# FRA_Sensor_v1.net
KiCad netlist of a schematic drawn in EAGLE
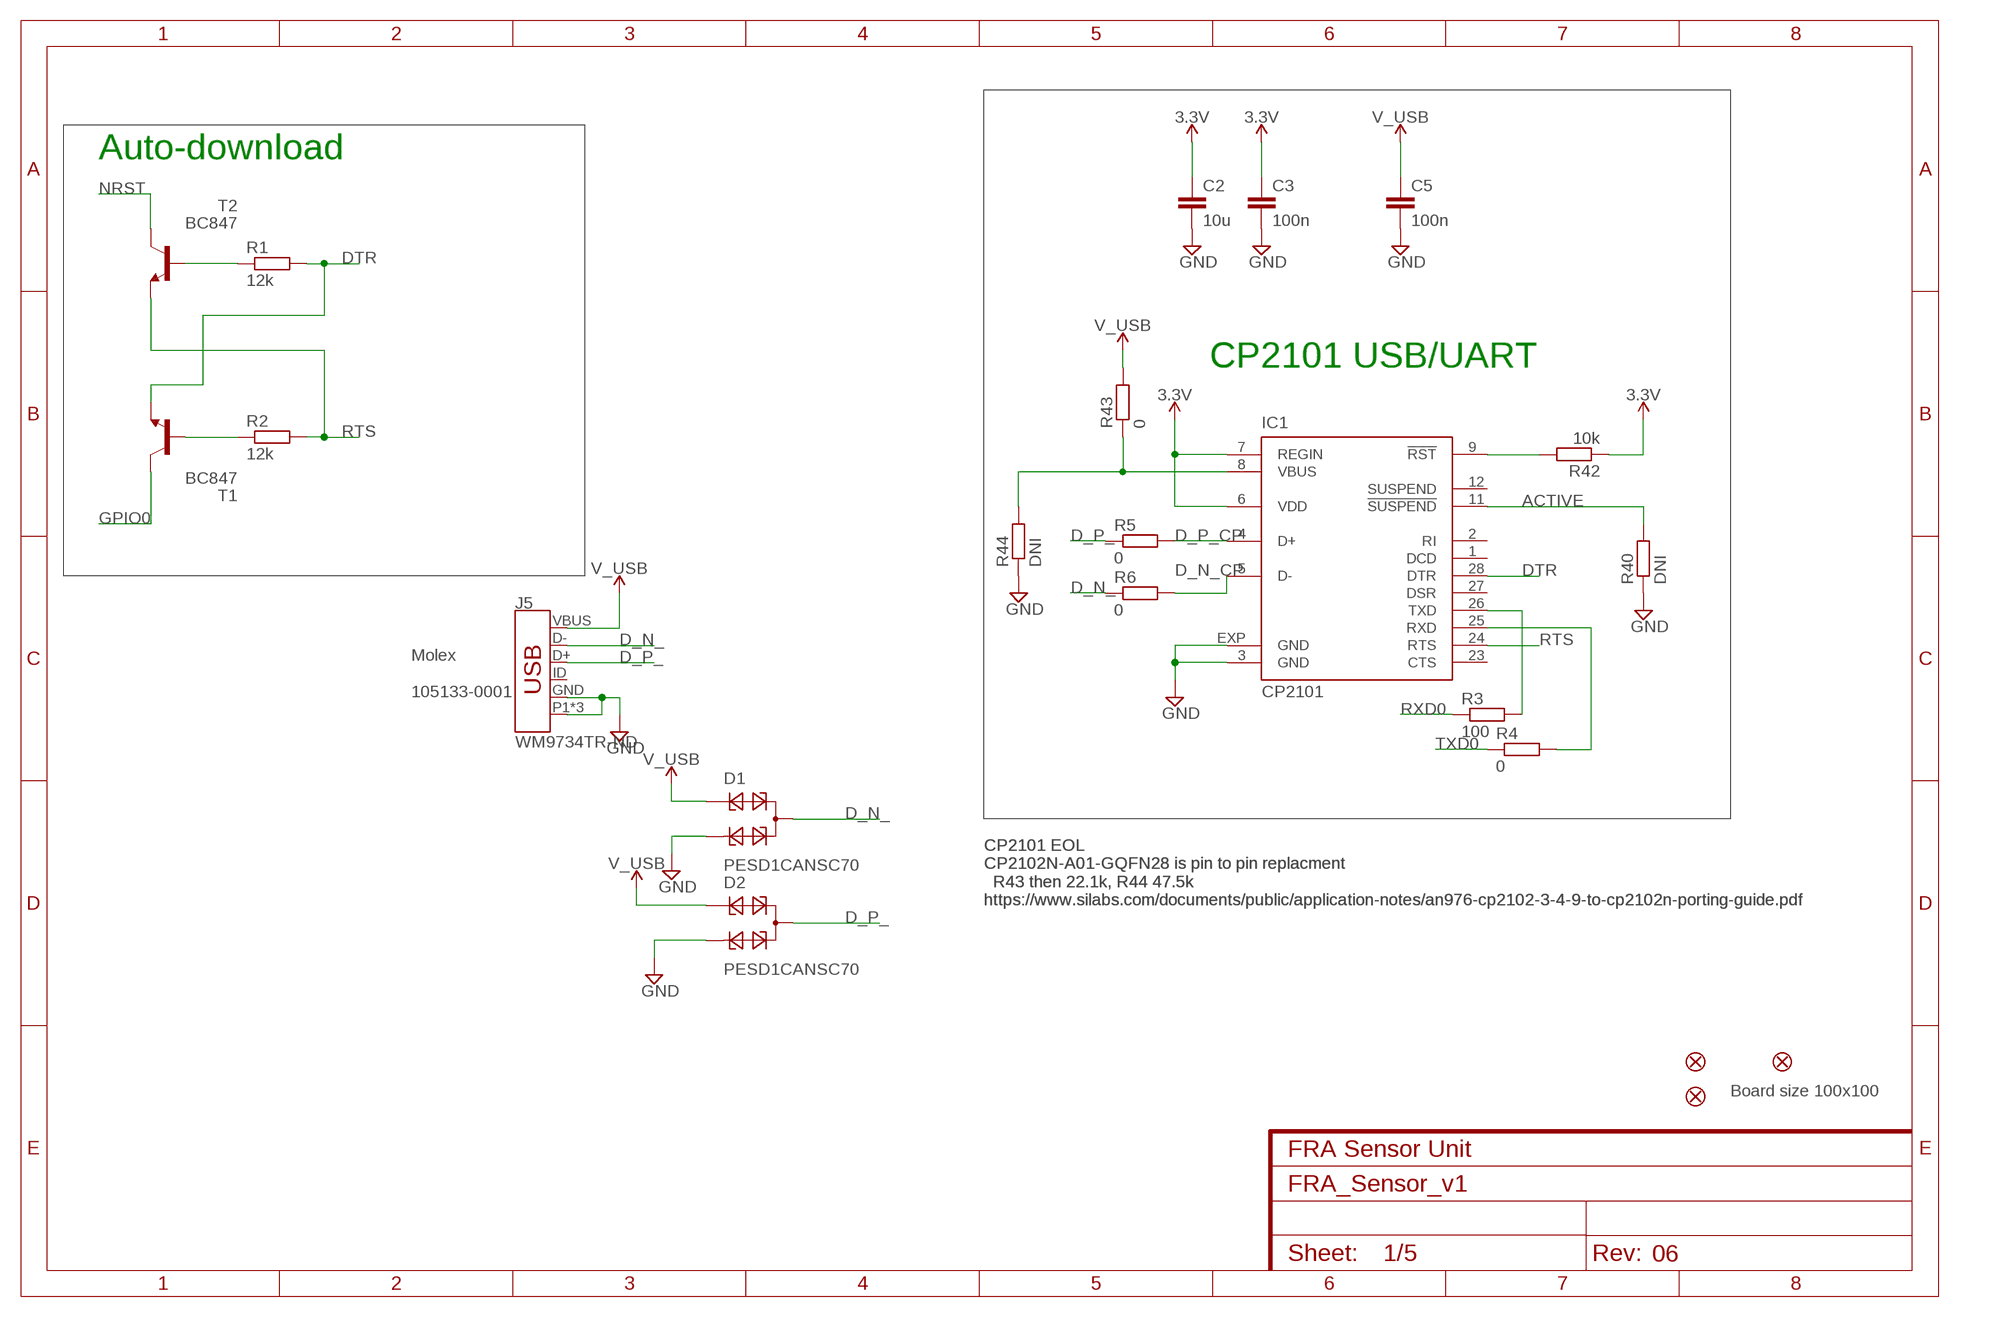
[diagram p0: schematic, sheet 1]
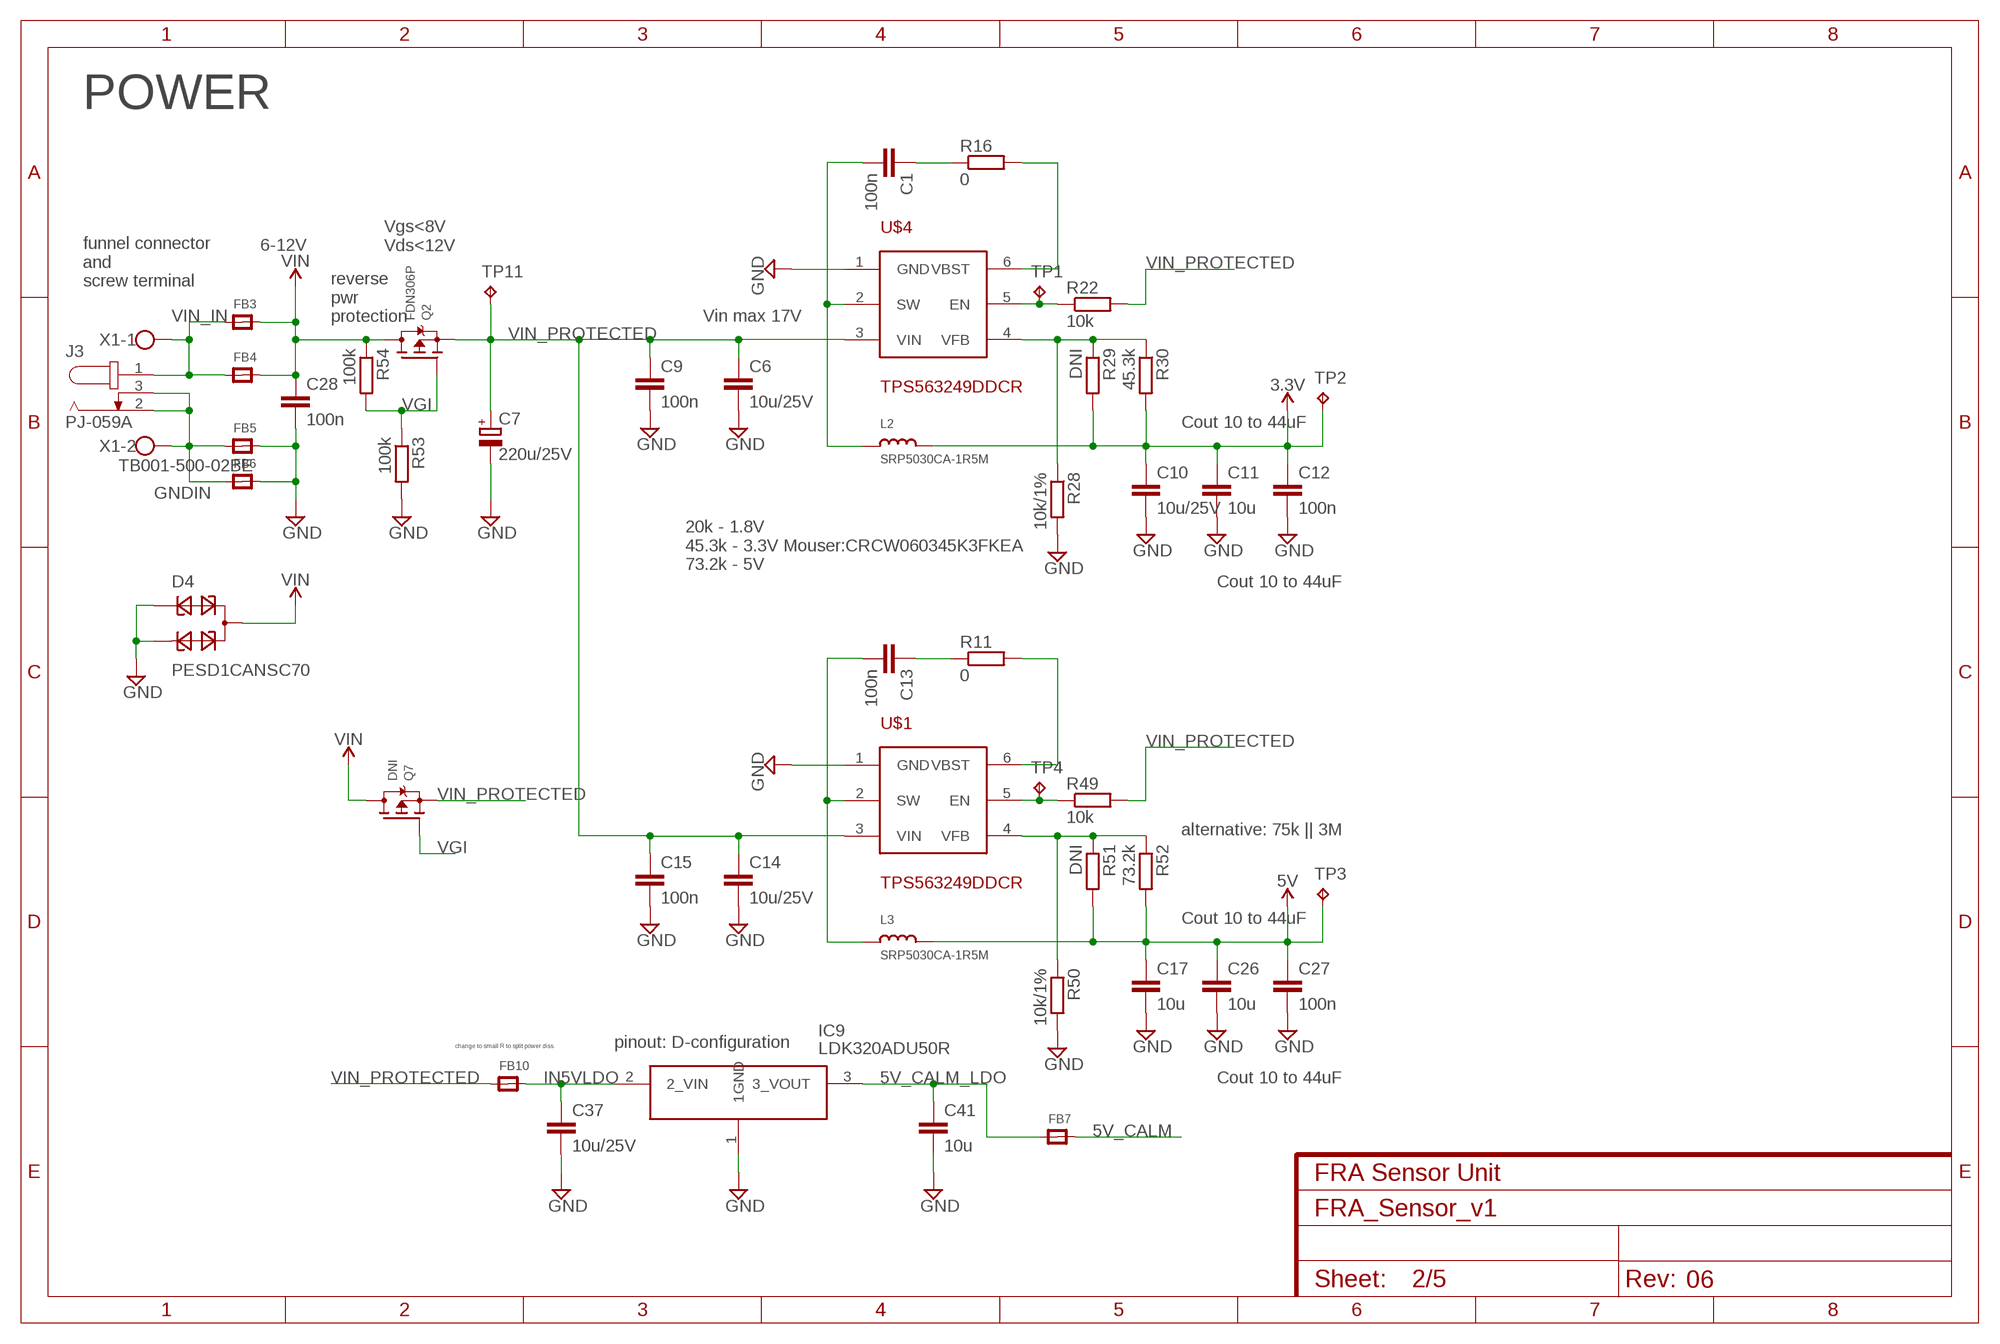
[diagram p1: schematic, sheet 2]
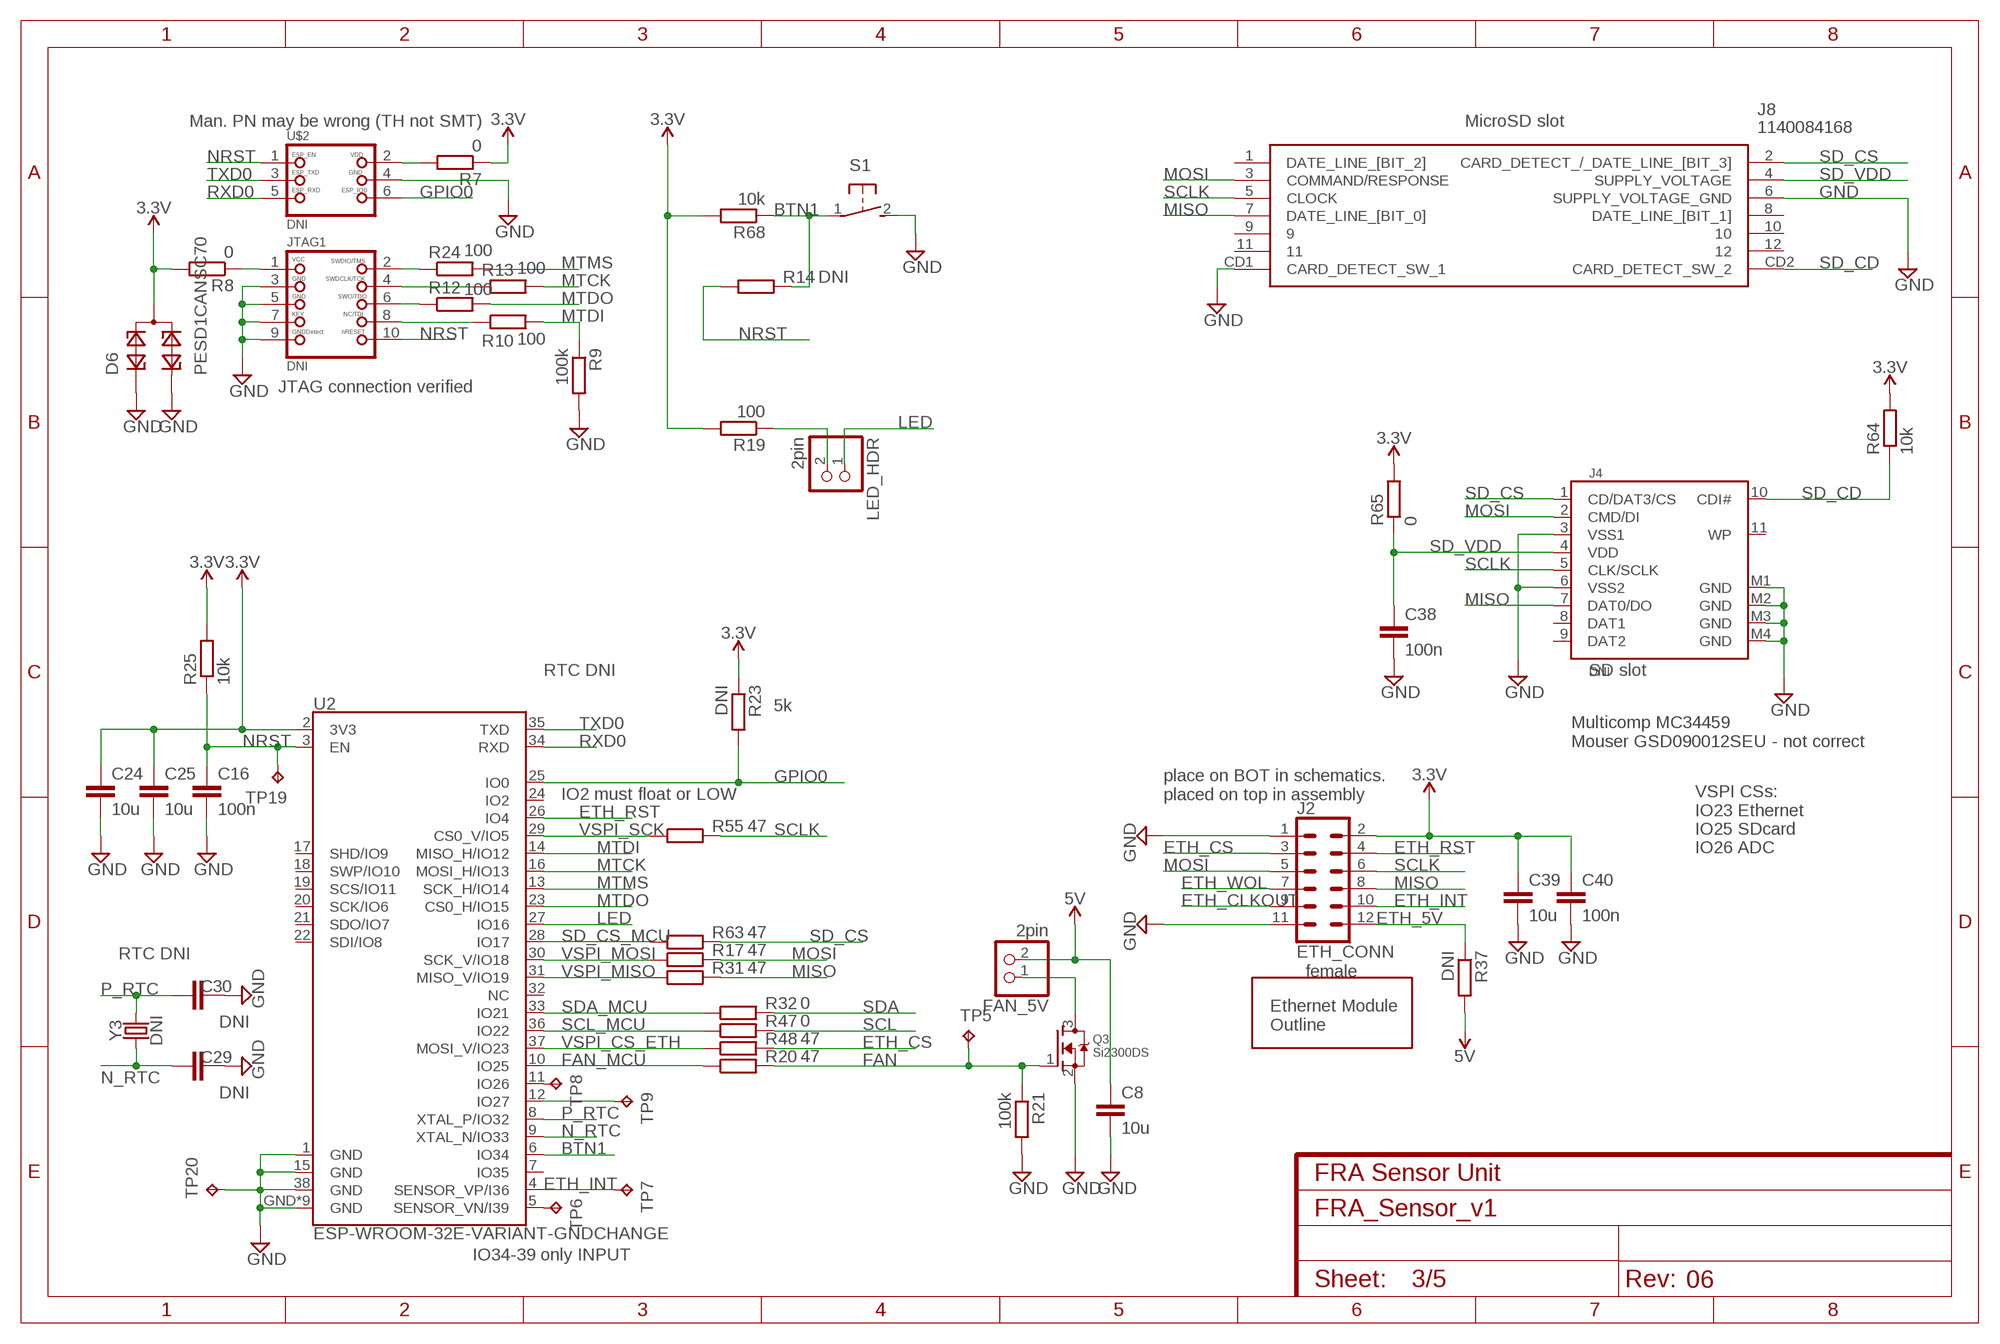
[diagram p2: schematic, sheet 3]
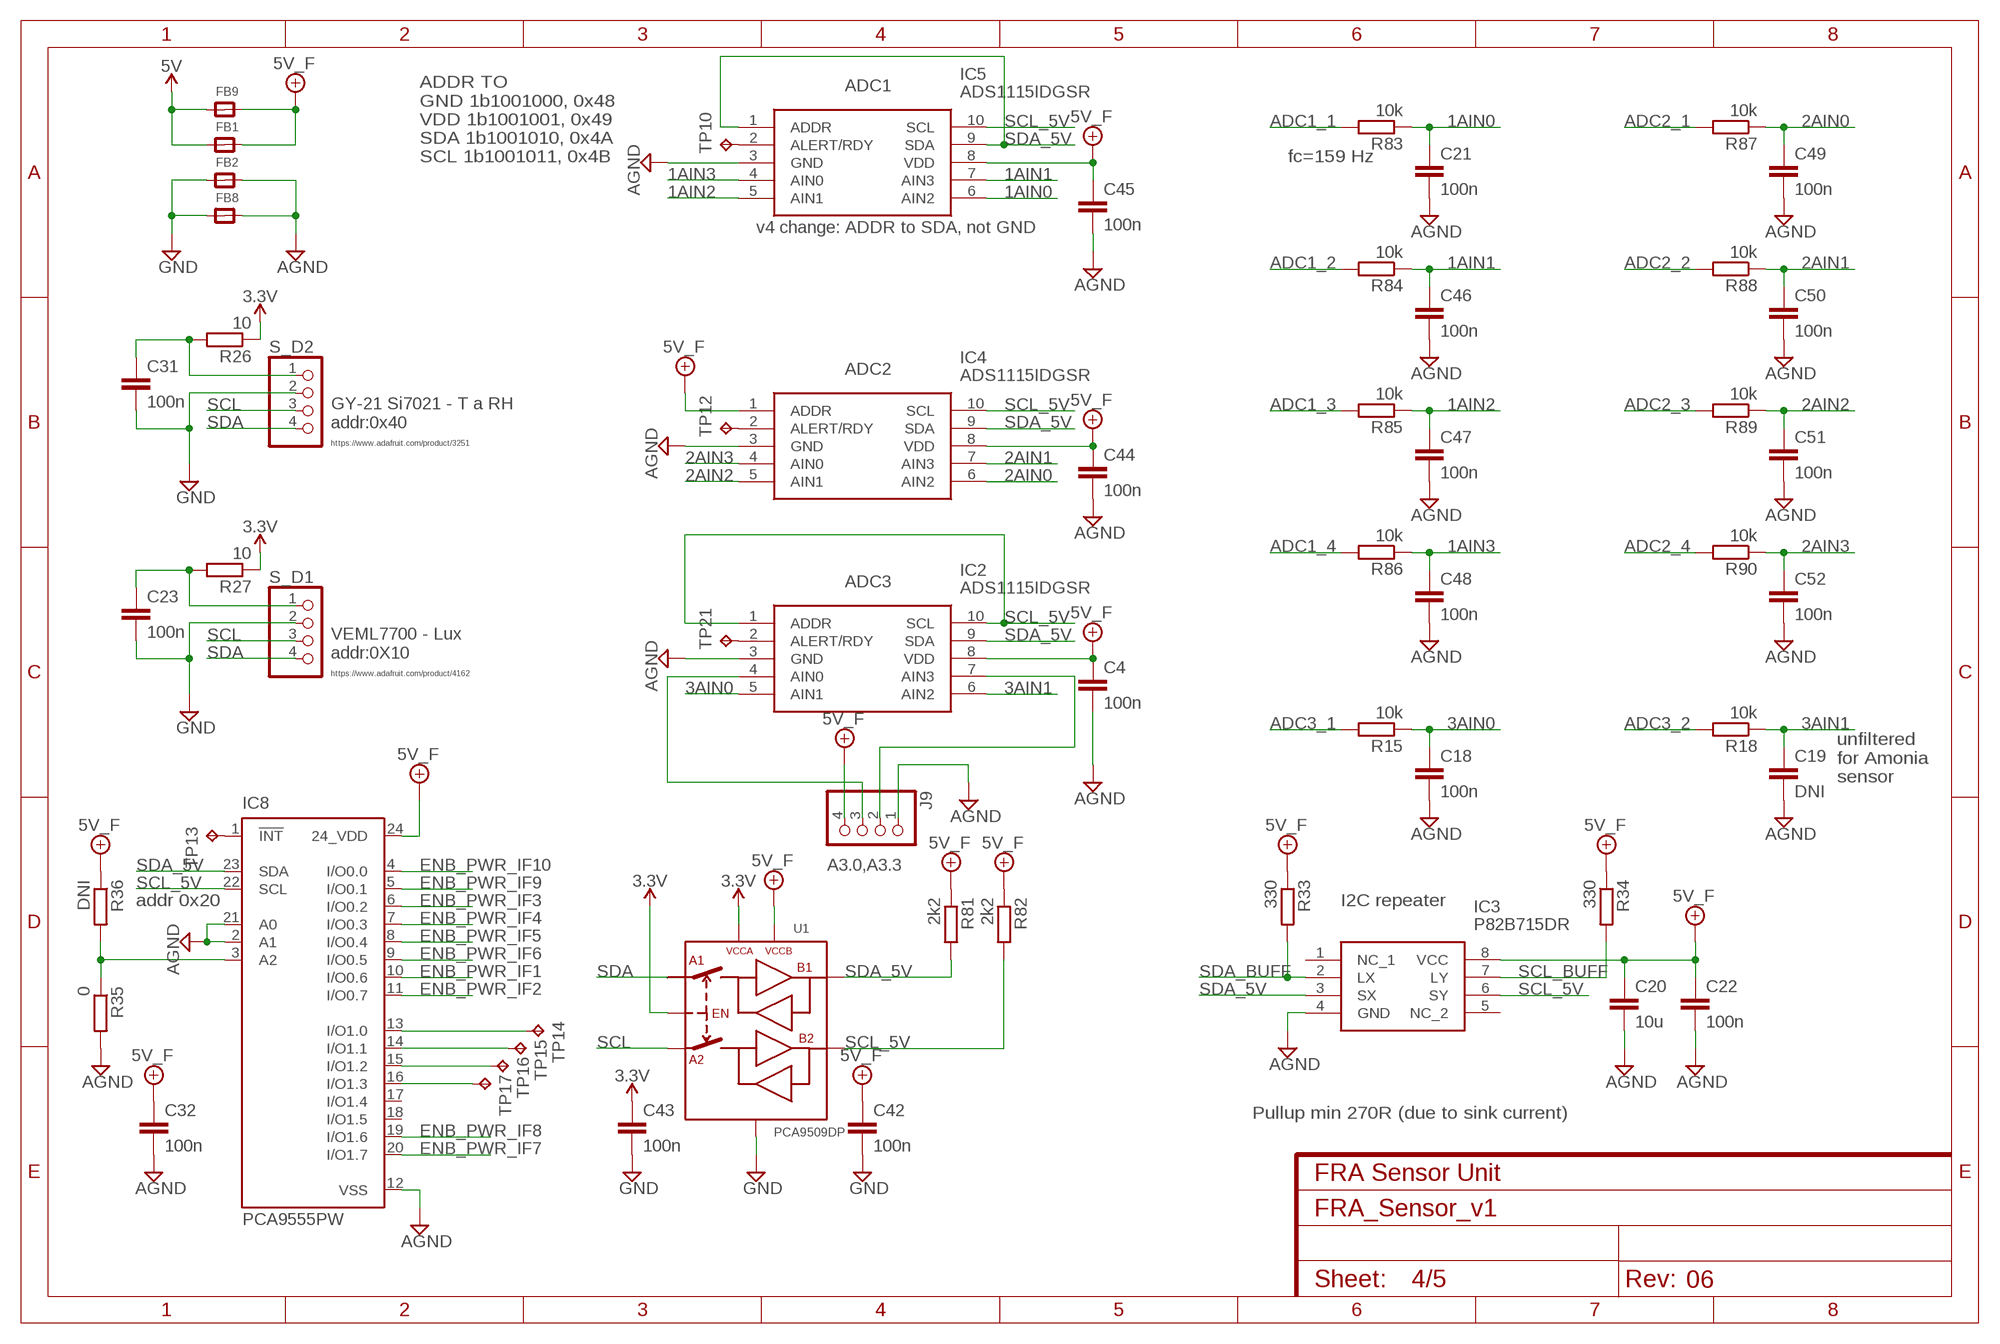
[diagram p3: schematic, sheet 4]
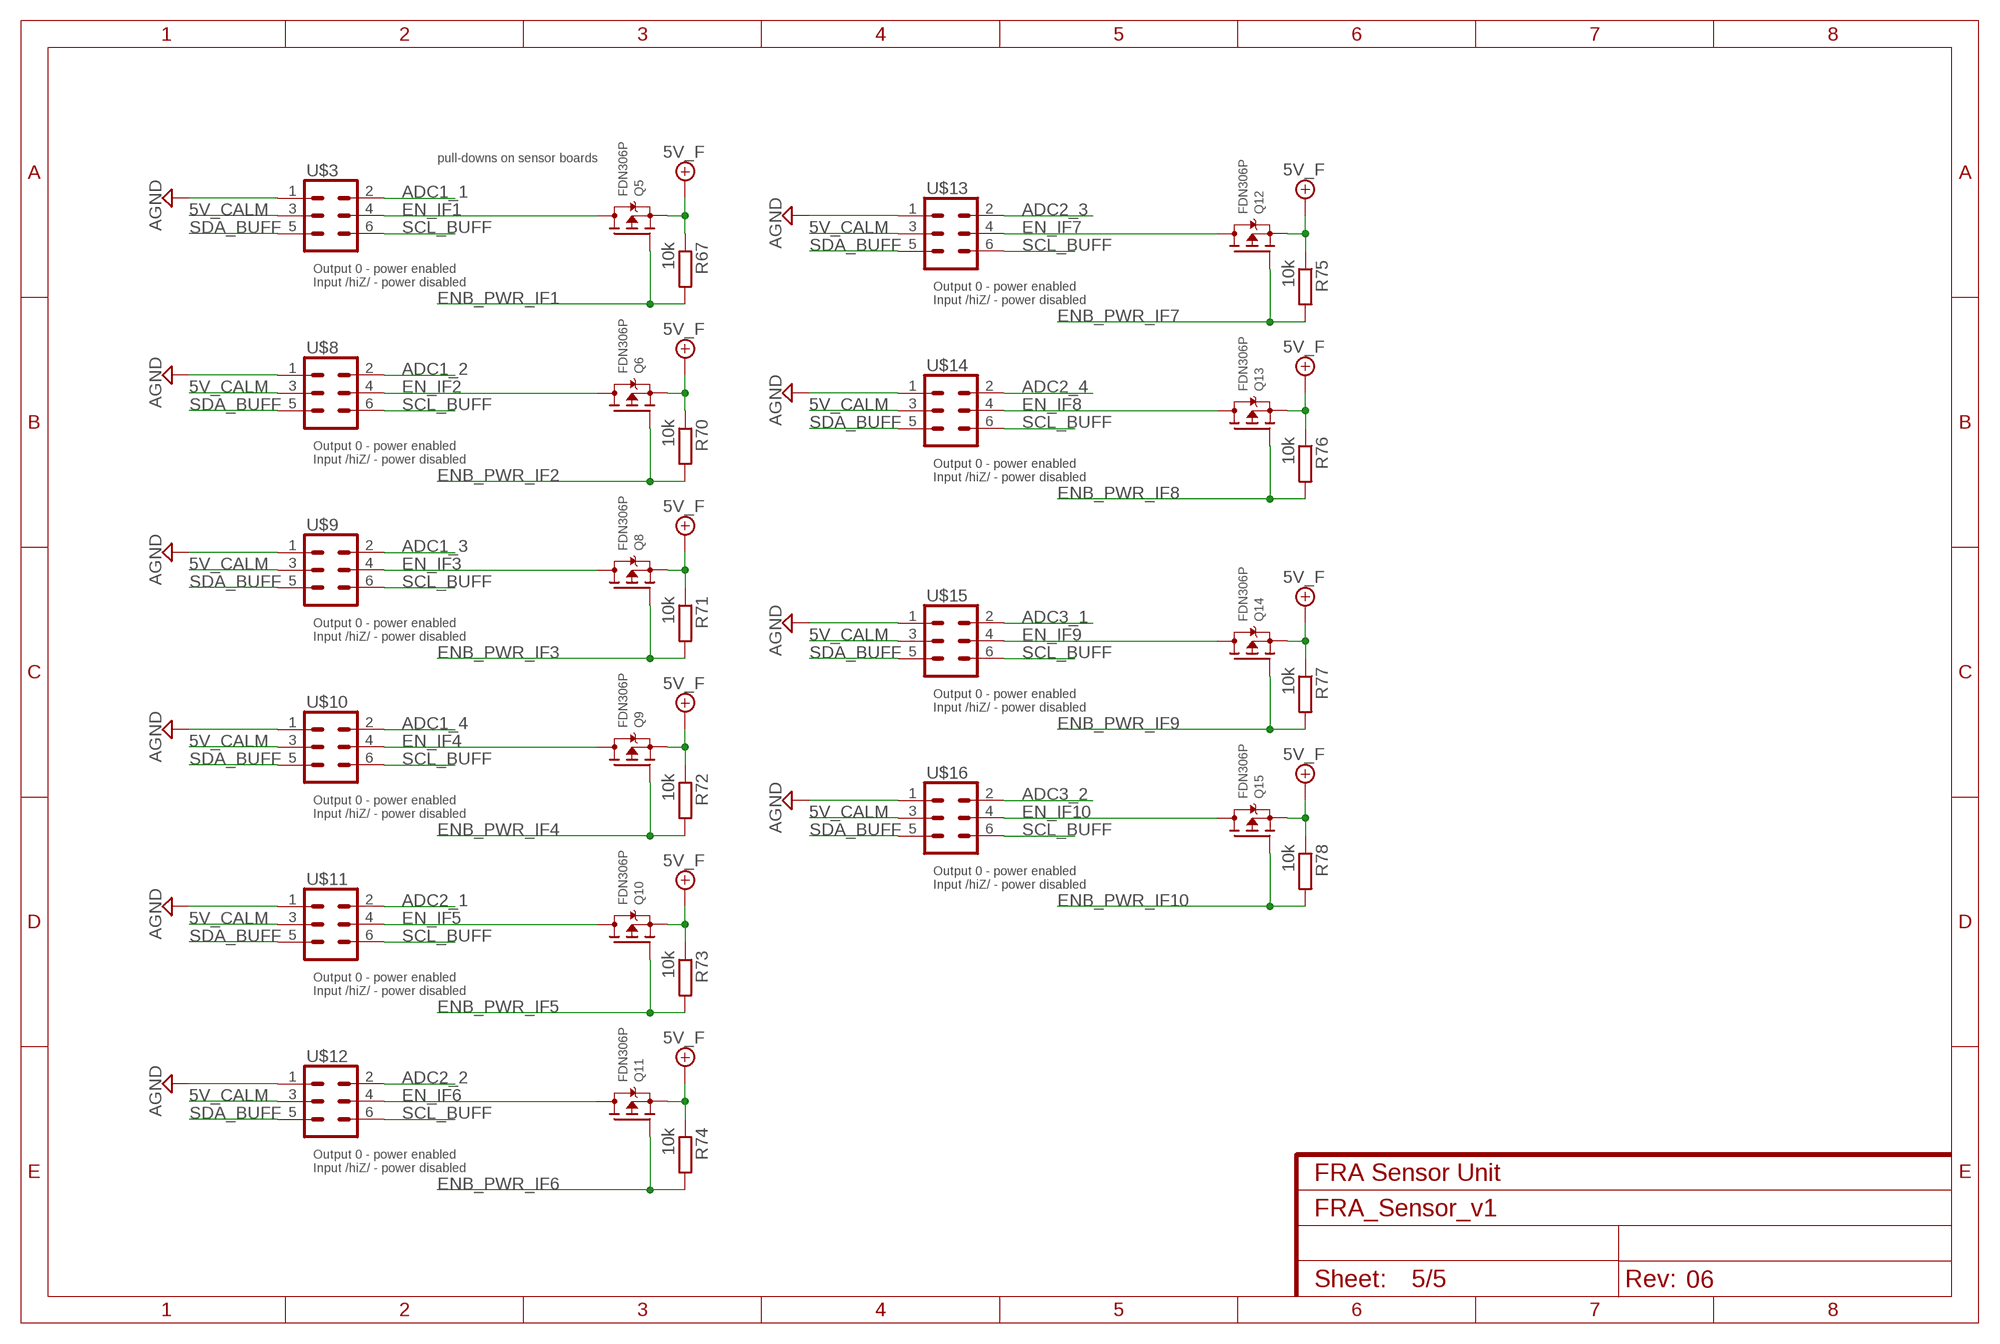
[diagram p4: schematic, sheet 5]

(export (version "E")
  (design (tool "Eeschema 10.0.6"))
  (components
    (comp (ref "C4")
      (value "100n")
      (footprint "eagle-import:C0603K")
      (fields (field (name "PARTNO") "CC0603KRX7R8BB104"))
      (libsource (lib "eagle-import") (part "C-EUC0603K"))
    )
    (comp (ref "C18")
      (value "100n")
      (footprint "eagle-import:C0603K")
      (fields (field (name "PARTNO") "CC0603KRX7R8BB104"))
      (libsource (lib "eagle-import") (part "C-EUC0603K"))
    )
    (comp (ref "C19")
      (value "DNI")
      (footprint "eagle-import:C0603K")
      (fields (field (name "PARTNO") "CC0603KRX7R8BB104"))
      (libsource (lib "eagle-import") (part "C-EUC0603K"))
    )
    (comp (ref "C20")
      (value "10u")
      (footprint "eagle-import:C0603K")
      (fields (field (name "PARTNO") "GRM188R61A106KE69J"))
      (libsource (lib "eagle-import") (part "C-EUC0603K"))
    )
    (comp (ref "C21")
      (value "100n")
      (footprint "eagle-import:C0603K")
      (fields (field (name "PARTNO") "CC0603KRX7R8BB104"))
      (libsource (lib "eagle-import") (part "C-EUC0603K"))
    )
    (comp (ref "C22")
      (value "100n")
      (footprint "eagle-import:C0603K")
      (fields (field (name "PARTNO") "CC0603KRX7R8BB104"))
      (libsource (lib "eagle-import") (part "C-EUC0603K"))
    )
    (comp (ref "C23")
      (value "100n")
      (footprint "eagle-import:C0603K")
      (fields (field (name "PARTNO") "CC0603KRX7R8BB104"))
      (libsource (lib "eagle-import") (part "C-EUC0603K"))
    )
    (comp (ref "C31")
      (value "100n")
      (footprint "eagle-import:C0603K")
      (fields (field (name "PARTNO") "CC0603KRX7R8BB104"))
      (libsource (lib "eagle-import") (part "C-EUC0603K"))
    )
    (comp (ref "C32")
      (value "100n")
      (footprint "eagle-import:C0603K")
      (fields (field (name "PARTNO") "CC0603KRX7R8BB104"))
      (libsource (lib "eagle-import") (part "C-EUC0603K"))
    )
    (comp (ref "C42")
      (value "100n")
      (footprint "eagle-import:C0603K")
      (fields (field (name "PARTNO") "CC0603KRX7R8BB104"))
      (libsource (lib "eagle-import") (part "C-EUC0603K"))
    )
    (comp (ref "C43")
      (value "100n")
      (footprint "eagle-import:C0603K")
      (fields (field (name "PARTNO") "CC0603KRX7R8BB104"))
      (libsource (lib "eagle-import") (part "C-EUC0603K"))
    )
    (comp (ref "C44")
      (value "100n")
      (footprint "eagle-import:C0603K")
      (fields (field (name "PARTNO") "CC0603KRX7R8BB104"))
      (libsource (lib "eagle-import") (part "C-EUC0603K"))
    )
    (comp (ref "C45")
      (value "100n")
      (footprint "eagle-import:C0603K")
      (fields (field (name "PARTNO") "CC0603KRX7R8BB104"))
      (libsource (lib "eagle-import") (part "C-EUC0603K"))
    )
    (comp (ref "C46")
      (value "100n")
      (footprint "eagle-import:C0603K")
      (fields (field (name "PARTNO") "CC0603KRX7R8BB104"))
      (libsource (lib "eagle-import") (part "C-EUC0603K"))
    )
    (comp (ref "C47")
      (value "100n")
      (footprint "eagle-import:C0603K")
      (fields (field (name "PARTNO") "CC0603KRX7R8BB104"))
      (libsource (lib "eagle-import") (part "C-EUC0603K"))
    )
    (comp (ref "C48")
      (value "100n")
      (footprint "eagle-import:C0603K")
      (fields (field (name "PARTNO") "CC0603KRX7R8BB104"))
      (libsource (lib "eagle-import") (part "C-EUC0603K"))
    )
    (comp (ref "C49")
      (value "100n")
      (footprint "eagle-import:C0603K")
      (fields (field (name "PARTNO") "CC0603KRX7R8BB104"))
      (libsource (lib "eagle-import") (part "C-EUC0603K"))
    )
    (comp (ref "C50")
      (value "100n")
      (footprint "eagle-import:C0603K")
      (fields (field (name "PARTNO") "CC0603KRX7R8BB104"))
      (libsource (lib "eagle-import") (part "C-EUC0603K"))
    )
    (comp (ref "C51")
      (value "100n")
      (footprint "eagle-import:C0603K")
      (fields (field (name "PARTNO") "CC0603KRX7R8BB104"))
      (libsource (lib "eagle-import") (part "C-EUC0603K"))
    )
    (comp (ref "C52")
      (value "100n")
      (footprint "eagle-import:C0603K")
      (fields (field (name "PARTNO") "CC0603KRX7R8BB104"))
      (libsource (lib "eagle-import") (part "C-EUC0603K"))
    )
    (comp (ref "FB1")
      (value "FERRITE")
      (footprint "eagle-import:0603")
      (fields (field (name "PARTNO") "BLM18PG121SN1D"))
      (libsource (lib "eagle-import") (part "FERRITE"))
    )
    (comp (ref "FB2")
      (value "FERRITE")
      (footprint "eagle-import:0603")
      (fields (field (name "PARTNO") "BLM18PG121SN1D"))
      (libsource (lib "eagle-import") (part "FERRITE"))
    )
    (comp (ref "FB8")
      (value "FERRITE")
      (footprint "eagle-import:0603")
      (fields (field (name "PARTNO") "BLM18PG121SN1D"))
      (libsource (lib "eagle-import") (part "FERRITE"))
    )
    (comp (ref "FB9")
      (value "FERRITE")
      (footprint "eagle-import:0603")
      (fields (field (name "PARTNO") "BLM18PG121SN1D"))
      (libsource (lib "eagle-import") (part "FERRITE"))
    )
    (comp (ref "IC2")
      (value "ADS1115IDGSR")
      (footprint "eagle-import:SOP50P490X110-10N")
      (fields
        (field (name "MANUFACTURER_PART_NUMBER") "ADS1115BQDGSRQ1")
        (field (name "MOUSER_PART_NUMBER") "595-ADS1115BQDGSRQ1")
      )
      (libsource (lib "eagle-import") (part "ADS1115BQDGSRQ1"))
    )
    (comp (ref "IC3")
      (value "P82B715DR")
      (footprint "eagle-import:SOIC127P600X175-8N")
      (libsource (lib "eagle-import") (part "P82B715DR"))
    )
    (comp (ref "IC4")
      (value "ADS1115IDGSR")
      (footprint "eagle-import:SOP50P490X110-10N")
      (fields
        (field (name "MANUFACTURER_PART_NUMBER") "ADS1115BQDGSRQ1")
        (field (name "MOUSER_PART_NUMBER") "595-ADS1115BQDGSRQ1")
      )
      (libsource (lib "eagle-import") (part "ADS1115BQDGSRQ1"))
    )
    (comp (ref "IC5")
      (value "ADS1115IDGSR")
      (footprint "eagle-import:SOP50P490X110-10N")
      (fields
        (field (name "MANUFACTURER_PART_NUMBER") "ADS1115BQDGSRQ1")
        (field (name "MOUSER_PART_NUMBER") "595-ADS1115BQDGSRQ1")
      )
      (libsource (lib "eagle-import") (part "ADS1115BQDGSRQ1"))
    )
    (comp (ref "IC8")
      (value "PCA9555PW")
      (footprint "eagle-import:TSSOP24")
      (fields (field (name "PARTNO") "PCA9555PW,118"))
      (libsource (lib "eagle-import") (part "PCA9555PW"))
    )
    (comp (ref "J9")
      (value "4pin")
      (footprint "eagle-import:1X04")
      (fields (field (name "PARTNO") "61300411121"))
      (libsource (lib "eagle-import") (part "PINHD-1X4"))
    )
    (comp (ref "R15")
      (value "10k")
      (footprint "eagle-import:R0603")
      (fields (field (name "PARTNO") "CRCW060310K0JNEAC"))
      (libsource (lib "eagle-import") (part "R-EU_R0603"))
    )
    (comp (ref "R18")
      (value "10k")
      (footprint "eagle-import:R0603")
      (fields (field (name "PARTNO") "CRCW060310K0JNEAC"))
      (libsource (lib "eagle-import") (part "R-EU_R0603"))
    )
    (comp (ref "R26")
      (value "10")
      (footprint "eagle-import:R0603")
      (fields (field (name "PARTNO") "CRCW060310R0FKEAC"))
      (libsource (lib "eagle-import") (part "R-EU_R0603"))
    )
    (comp (ref "R27")
      (value "10")
      (footprint "eagle-import:R0603")
      (fields (field (name "PARTNO") "CRCW060310R0FKEAC"))
      (libsource (lib "eagle-import") (part "R-EU_R0603"))
    )
    (comp (ref "R33")
      (value "330")
      (footprint "eagle-import:R0603")
      (fields (field (name "PARTNO") "CRCW0603330RFKEAC"))
      (libsource (lib "eagle-import") (part "R-EU_R0603"))
    )
    (comp (ref "R34")
      (value "330")
      (footprint "eagle-import:R0603")
      (fields (field (name "PARTNO") "CRCW0603330RFKEAC"))
      (libsource (lib "eagle-import") (part "R-EU_R0603"))
    )
    (comp (ref "R35")
      (value "0")
      (footprint "eagle-import:R0603")
      (fields (field (name "PARTNO") "CRCW06030000Z0EAC"))
      (libsource (lib "eagle-import") (part "R-EU_R0603"))
    )
    (comp (ref "R36")
      (value "DNI")
      (footprint "eagle-import:R0603")
      (fields (field (name "PARTNO") "CRCW0603330RFKEAC"))
      (libsource (lib "eagle-import") (part "R-EU_R0603"))
    )
    (comp (ref "R81")
      (value "2k2")
      (footprint "eagle-import:R0603")
      (fields (field (name "PARTNO") "RCS06032K20JNEA"))
      (libsource (lib "eagle-import") (part "R-EU_R0603"))
    )
    (comp (ref "R82")
      (value "2k2")
      (footprint "eagle-import:R0603")
      (fields (field (name "PARTNO") "RCS06032K20JNEA"))
      (libsource (lib "eagle-import") (part "R-EU_R0603"))
    )
    (comp (ref "R83")
      (value "10k")
      (footprint "eagle-import:R0603")
      (fields (field (name "PARTNO") "CRCW060310K0JNEAC"))
      (libsource (lib "eagle-import") (part "R-EU_R0603"))
    )
    (comp (ref "R84")
      (value "10k")
      (footprint "eagle-import:R0603")
      (fields (field (name "PARTNO") "CRCW060310K0JNEAC"))
      (libsource (lib "eagle-import") (part "R-EU_R0603"))
    )
    (comp (ref "R85")
      (value "10k")
      (footprint "eagle-import:R0603")
      (fields (field (name "PARTNO") "CRCW060310K0JNEAC"))
      (libsource (lib "eagle-import") (part "R-EU_R0603"))
    )
    (comp (ref "R86")
      (value "10k")
      (footprint "eagle-import:R0603")
      (fields (field (name "PARTNO") "CRCW060310K0JNEAC"))
      (libsource (lib "eagle-import") (part "R-EU_R0603"))
    )
    (comp (ref "R87")
      (value "10k")
      (footprint "eagle-import:R0603")
      (fields (field (name "PARTNO") "CRCW060310K0JNEAC"))
      (libsource (lib "eagle-import") (part "R-EU_R0603"))
    )
    (comp (ref "R88")
      (value "10k")
      (footprint "eagle-import:R0603")
      (fields (field (name "PARTNO") "CRCW060310K0JNEAC"))
      (libsource (lib "eagle-import") (part "R-EU_R0603"))
    )
    (comp (ref "R89")
      (value "10k")
      (footprint "eagle-import:R0603")
      (fields (field (name "PARTNO") "CRCW060310K0JNEAC"))
      (libsource (lib "eagle-import") (part "R-EU_R0603"))
    )
    (comp (ref "R90")
      (value "10k")
      (footprint "eagle-import:R0603")
      (fields (field (name "PARTNO") "CRCW060310K0JNEAC"))
      (libsource (lib "eagle-import") (part "R-EU_R0603"))
    )
    (comp (ref "S_D1")
      (value "4pin")
      (footprint "eagle-import:1X04")
      (fields (field (name "PARTNO") "61300411121"))
      (libsource (lib "eagle-import") (part "PINHD-1X4"))
    )
    (comp (ref "S_D2")
      (value "4pin")
      (footprint "eagle-import:1X04")
      (fields (field (name "PARTNO") "61300411121"))
      (libsource (lib "eagle-import") (part "PINHD-1X4"))
    )
    (comp (ref "TP10")
      (value "TPTP10R")
      (footprint "eagle-import:TP10R")
      (libsource (lib "eagle-import") (part "TPTP10R"))
    )
    (comp (ref "TP12")
      (value "TPTP10R")
      (footprint "eagle-import:TP10R")
      (libsource (lib "eagle-import") (part "TPTP10R"))
    )
    (comp (ref "TP13")
      (value "TPTP10R")
      (footprint "eagle-import:TP10R")
      (libsource (lib "eagle-import") (part "TPTP10R"))
    )
    (comp (ref "TP14")
      (value "TPTP10R")
      (footprint "eagle-import:TP10R")
      (libsource (lib "eagle-import") (part "TPTP10R"))
    )
    (comp (ref "TP15")
      (value "TPTP10R")
      (footprint "eagle-import:TP10R")
      (libsource (lib "eagle-import") (part "TPTP10R"))
    )
    (comp (ref "TP16")
      (value "TPTP10R")
      (footprint "eagle-import:TP10R")
      (libsource (lib "eagle-import") (part "TPTP10R"))
    )
    (comp (ref "TP17")
      (value "TPTP10R")
      (footprint "eagle-import:TP10R")
      (libsource (lib "eagle-import") (part "TPTP10R"))
    )
    (comp (ref "TP21")
      (value "TPTP10R")
      (footprint "eagle-import:TP10R")
      (libsource (lib "eagle-import") (part "TPTP10R"))
    )
    (comp (ref "U1")
      (value "PCA9509DP")
      (footprint "eagle-import:SOT505-1")
      (fields (field (name "PARTNO") "PCA9509DP,118"))
      (libsource (lib "eagle-import") (part "PCA9509DP"))
    )
    (comp (ref "C2")
      (value "10u")
      (footprint "eagle-import:C0603K")
      (fields (field (name "PARTNO") "GRM188R61A106KE69J"))
      (libsource (lib "eagle-import") (part "C-EUC0603K"))
    )
    (comp (ref "C3")
      (value "100n")
      (footprint "eagle-import:C0603K")
      (fields (field (name "PARTNO") "CC0603KRX7R8BB104"))
      (libsource (lib "eagle-import") (part "C-EUC0603K"))
    )
    (comp (ref "C5")
      (value "100n")
      (footprint "eagle-import:C0603K")
      (fields (field (name "PARTNO") "CC0603KRX7R8BB104"))
      (libsource (lib "eagle-import") (part "C-EUC0603K"))
    )
    (comp (ref "D1")
      (value "PESD1CANSC70")
      (footprint "eagle-import:SOT323-R")
      (fields (field (name "PARTNO") "PESD1CAN-UX"))
      (libsource (lib "eagle-import") (part "PESD1CANSC70"))
    )
    (comp (ref "D2")
      (value "PESD1CANSC70")
      (footprint "eagle-import:SOT323-R")
      (fields (field (name "PARTNO") "PESD1CAN-UX"))
      (libsource (lib "eagle-import") (part "PESD1CANSC70"))
    )
    (comp (ref "FID1")
      (value "FIDUCIAL\"\"")
      (footprint "eagle-import:FIDUCIAL_1MM")
      (libsource (lib "eagle-import") (part "FIDUCIAL{dblquote}{dblquote}"))
    )
    (comp (ref "FID2")
      (value "FIDUCIAL\"\"")
      (footprint "eagle-import:FIDUCIAL_1MM")
      (libsource (lib "eagle-import") (part "FIDUCIAL{dblquote}{dblquote}"))
    )
    (comp (ref "FID4")
      (value "FIDUCIAL\"\"")
      (footprint "eagle-import:FIDUCIAL_1MM")
      (libsource (lib "eagle-import") (part "FIDUCIAL{dblquote}{dblquote}"))
    )
    (comp (ref "IC1")
      (value "CP2101")
      (footprint "eagle-import:MLP28")
      (fields (field (name "PARTNO") "CP2101-GM"))
      (libsource (lib "eagle-import") (part "CP210X_USB_UART"))
    )
    (comp (ref "J5")
      (value "WM9734TR-ND")
      (footprint "eagle-import:USB-B-MICRO-SMD_VERT")
      (fields (field (name "PARTNO") "105133-0001"))
      (libsource (lib "eagle-import") (part "USB_MICRO-B_FEMALE-SMT-VERT"))
    )
    (comp (ref "R1")
      (value "12k")
      (footprint "eagle-import:R0603")
      (fields (field (name "PARTNO") "RC0603FR-0712KL"))
      (libsource (lib "eagle-import") (part "R-EU_R0603"))
    )
    (comp (ref "R2")
      (value "12k")
      (footprint "eagle-import:R0603")
      (fields (field (name "PARTNO") "RC0603FR-0712KL"))
      (libsource (lib "eagle-import") (part "R-EU_R0603"))
    )
    (comp (ref "R3")
      (value "100")
      (footprint "eagle-import:R0603")
      (fields (field (name "PARTNO") "CRCW0603100RFKEAC"))
      (libsource (lib "eagle-import") (part "R-EU_R0603"))
    )
    (comp (ref "R4")
      (value "0")
      (footprint "eagle-import:R0603")
      (fields (field (name "PARTNO") "CRCW06030000Z0EAC"))
      (libsource (lib "eagle-import") (part "R-EU_R0603"))
    )
    (comp (ref "R5")
      (value "0")
      (footprint "eagle-import:R0603")
      (fields (field (name "PARTNO") "CRCW06030000Z0EAC"))
      (libsource (lib "eagle-import") (part "R-EU_R0603"))
    )
    (comp (ref "R6")
      (value "0")
      (footprint "eagle-import:R0603")
      (fields (field (name "PARTNO") "CRCW06030000Z0EAC"))
      (libsource (lib "eagle-import") (part "R-EU_R0603"))
    )
    (comp (ref "R40")
      (value "DNI")
      (footprint "eagle-import:R0603")
      (fields (field (name "PARTNO") "CRCW06030000Z0EAC"))
      (libsource (lib "eagle-import") (part "R-EU_R0603"))
    )
    (comp (ref "R42")
      (value "10k")
      (footprint "eagle-import:R0603")
      (fields (field (name "PARTNO") "CRCW060310K0JNEAC"))
      (libsource (lib "eagle-import") (part "R-EU_R0603"))
    )
    (comp (ref "R43")
      (value "0")
      (footprint "eagle-import:R0603")
      (fields (field (name "PARTNO") "CRCW06030000Z0EAC"))
      (libsource (lib "eagle-import") (part "R-EU_R0603"))
    )
    (comp (ref "R44")
      (value "DNI")
      (footprint "eagle-import:R0603")
      (fields (field (name "PARTNO") "CRCW06030000Z0EAC"))
      (libsource (lib "eagle-import") (part "R-EU_R0603"))
    )
    (comp (ref "T1")
      (value "BC847")
      (footprint "eagle-import:SOT23")
      (fields (field (name "PARTNO") "BC847A-TP"))
      (libsource (lib "eagle-import") (part "BC847"))
    )
    (comp (ref "T2")
      (value "BC847")
      (footprint "eagle-import:SOT23")
      (fields (field (name "PARTNO") "BC847A-TP"))
      (libsource (lib "eagle-import") (part "BC847"))
    )
    (comp (ref "C1")
      (value "100n")
      (footprint "eagle-import:C0603K")
      (fields (field (name "PARTNO") "CC0603KRX7R8BB104"))
      (libsource (lib "eagle-import") (part "C-EUC0603K"))
    )
    (comp (ref "C6")
      (value "10u/25V")
      (footprint "eagle-import:C0603K")
      (fields (field (name "PARTNO") "GRM188R61E106KA73J"))
      (libsource (lib "eagle-import") (part "C-EUC0603K"))
    )
    (comp (ref "C7")
      (value "220u/25V")
      (footprint "eagle-import:153CLV-0605")
      (fields (field (name "PARTNO") "EMZR250ARA221MF80G"))
      (libsource (lib "eagle-import") (part "CPOL-EU153CLV-0605"))
    )
    (comp (ref "C9")
      (value "100n")
      (footprint "eagle-import:C0603K")
      (fields (field (name "PARTNO") "CC0603KRX7R8BB104"))
      (libsource (lib "eagle-import") (part "C-EUC0603K"))
    )
    (comp (ref "C10")
      (value "10u/25V")
      (footprint "eagle-import:C0603K")
      (fields (field (name "PARTNO") "GRM188R61E106KA73J"))
      (libsource (lib "eagle-import") (part "C-EUC0603K"))
    )
    (comp (ref "C11")
      (value "10u")
      (footprint "eagle-import:C0603K")
      (fields (field (name "PARTNO") "GRM188R61A106KE69J"))
      (libsource (lib "eagle-import") (part "C-EUC0603K"))
    )
    (comp (ref "C12")
      (value "100n")
      (footprint "eagle-import:C0603K")
      (fields (field (name "PARTNO") "CC0603KRX7R8BB104"))
      (libsource (lib "eagle-import") (part "C-EUC0603K"))
    )
    (comp (ref "C13")
      (value "100n")
      (footprint "eagle-import:C0603K")
      (fields (field (name "PARTNO") "CC0603KRX7R8BB104"))
      (libsource (lib "eagle-import") (part "C-EUC0603K"))
    )
    (comp (ref "C14")
      (value "10u/25V")
      (footprint "eagle-import:C0603K")
      (fields (field (name "PARTNO") "GRM188R61E106KA73J"))
      (libsource (lib "eagle-import") (part "C-EUC0603K"))
    )
    (comp (ref "C15")
      (value "100n")
      (footprint "eagle-import:C0603K")
      (fields (field (name "PARTNO") "CC0603KRX7R8BB104"))
      (libsource (lib "eagle-import") (part "C-EUC0603K"))
    )
    (comp (ref "C17")
      (value "10u")
      (footprint "eagle-import:C0603K")
      (fields (field (name "PARTNO") "GRM188R61A106KE69J"))
      (libsource (lib "eagle-import") (part "C-EUC0603K"))
    )
    (comp (ref "C26")
      (value "10u")
      (footprint "eagle-import:C0603K")
      (fields (field (name "PARTNO") "GRM188R61A106KE69J"))
      (libsource (lib "eagle-import") (part "C-EUC0603K"))
    )
    (comp (ref "C27")
      (value "100n")
      (footprint "eagle-import:C0603K")
      (fields (field (name "PARTNO") "CC0603KRX7R8BB104"))
      (libsource (lib "eagle-import") (part "C-EUC0603K"))
    )
    (comp (ref "C28")
      (value "100n")
      (footprint "eagle-import:C0603K")
      (fields (field (name "PARTNO") "CC0603KRX7R8BB104"))
      (libsource (lib "eagle-import") (part "C-EUC0603K"))
    )
    (comp (ref "C37")
      (value "10u/25V")
      (footprint "eagle-import:C0603K")
      (fields (field (name "PARTNO") "GRM188R61E106KA73J"))
      (libsource (lib "eagle-import") (part "C-EUC0603K"))
    )
    (comp (ref "C41")
      (value "10u")
      (footprint "eagle-import:C0603K")
      (fields (field (name "PARTNO") "GRM188R61A106KE69J"))
      (libsource (lib "eagle-import") (part "C-EUC0603K"))
    )
    (comp (ref "D4")
      (value "PESD1CANSC70")
      (footprint "eagle-import:SOT323-R")
      (fields (field (name "PARTNO") "PESD1CAN-UX"))
      (libsource (lib "eagle-import") (part "PESD1CANSC70"))
    )
    (comp (ref "FB3")
      (value "FERRITE")
      (footprint "eagle-import:0603")
      (fields (field (name "PARTNO") "BLM18PG121SN1D"))
      (libsource (lib "eagle-import") (part "FERRITE"))
    )
    (comp (ref "FB4")
      (value "FERRITE")
      (footprint "eagle-import:0603")
      (fields (field (name "PARTNO") "BLM18PG121SN1D"))
      (libsource (lib "eagle-import") (part "FERRITE"))
    )
    (comp (ref "FB5")
      (value "FERRITE")
      (footprint "eagle-import:0603")
      (fields (field (name "PARTNO") "BLM18PG121SN1D"))
      (libsource (lib "eagle-import") (part "FERRITE"))
    )
    (comp (ref "FB6")
      (value "FERRITE")
      (footprint "eagle-import:0603")
      (fields (field (name "PARTNO") "BLM18PG121SN1D"))
      (libsource (lib "eagle-import") (part "FERRITE"))
    )
    (comp (ref "FB7")
      (value "FERRITE")
      (footprint "eagle-import:0603")
      (fields (field (name "PARTNO") "BLM18PG121SN1D"))
      (libsource (lib "eagle-import") (part "FERRITE"))
    )
    (comp (ref "FB10")
      (value "FERRITE")
      (footprint "eagle-import:0603")
      (fields (field (name "PARTNO") "BLM18PG121SN1D"))
      (libsource (lib "eagle-import") (part "FERRITE"))
    )
    (comp (ref "IC9")
      (value "LDK320ADU50R")
      (footprint "eagle-import:ST-SOT-89")
      (fields (field (name "MOUSER_PART_NUMBER") "511-LDK320ADU50R"))
      (libsource (lib "eagle-import") (part "LDK320ADU50R"))
    )
    (comp (ref "J3")
      (value "PJ-059A")
      (footprint "eagle-import:PJ-059A")
      (fields (field (name "PARTNO") "PJ-059A "))
      (libsource (lib "eagle-import") (part "PJ-059A"))
    )
    (comp (ref "L2")
      (value "SRP5030CA-1R5M")
      (footprint "eagle-import:SRP5030CA")
      (fields (field (name "PARTNO") "SRP5030CA-1R5M "))
      (libsource (lib "eagle-import") (part "SRP5030CA-1R5M"))
    )
    (comp (ref "L3")
      (value "SRP5030CA-1R5M")
      (footprint "eagle-import:SRP5030CA")
      (fields (field (name "PARTNO") "SRP5030CA-1R5M "))
      (libsource (lib "eagle-import") (part "SRP5030CA-1R5M"))
    )
    (comp (ref "Q2")
      (value "FDN306P")
      (footprint "eagle-import:SOT23-WIDE")
      (libsource (lib "eagle-import") (part "MOSFET-PWIDE"))
    )
    (comp (ref "Q7")
      (value "DNI")
      (footprint "eagle-import:TO252")
      (libsource (lib "eagle-import") (part "MOSFET-PTO252"))
    )
    (comp (ref "R11")
      (value "0")
      (footprint "eagle-import:R0603")
      (fields (field (name "PARTNO") "CRCW06030000Z0EAC"))
      (libsource (lib "eagle-import") (part "R-EU_R0603"))
    )
    (comp (ref "R16")
      (value "0")
      (footprint "eagle-import:R0603")
      (fields (field (name "PARTNO") "CRCW06030000Z0EAC"))
      (libsource (lib "eagle-import") (part "R-EU_R0603"))
    )
    (comp (ref "R22")
      (value "10k")
      (footprint "eagle-import:R0603")
      (fields (field (name "PARTNO") "CRCW060310K0JNEAC"))
      (libsource (lib "eagle-import") (part "R-EU_R0603"))
    )
    (comp (ref "R28")
      (value "10k/1%")
      (footprint "eagle-import:R0603")
      (fields (field (name "PARTNO") "RN73R1JTTD1002D25"))
      (libsource (lib "eagle-import") (part "R-EU_R0603"))
    )
    (comp (ref "R29")
      (value "DNI")
      (footprint "eagle-import:R0603")
      (libsource (lib "eagle-import") (part "R-EU_R0603"))
    )
    (comp (ref "R30")
      (value "45.3k")
      (footprint "eagle-import:R0603")
      (fields (field (name "PARTNO") "ERJ-PB3D4532V"))
      (libsource (lib "eagle-import") (part "R-EU_R0603"))
    )
    (comp (ref "R49")
      (value "10k")
      (footprint "eagle-import:R0603")
      (fields (field (name "PARTNO") "CRCW060310K0JNEAC"))
      (libsource (lib "eagle-import") (part "R-EU_R0603"))
    )
    (comp (ref "R50")
      (value "10k/1%")
      (footprint "eagle-import:R0603")
      (fields (field (name "PARTNO") "RN73R1JTTD1002D25"))
      (libsource (lib "eagle-import") (part "R-EU_R0603"))
    )
    (comp (ref "R51")
      (value "DNI")
      (footprint "eagle-import:R0603")
      (libsource (lib "eagle-import") (part "R-EU_R0603"))
    )
    (comp (ref "R52")
      (value "73.2k")
      (footprint "eagle-import:R0603")
      (fields (field (name "PARTNO") "ERJ-PB3D7322V"))
      (libsource (lib "eagle-import") (part "R-EU_R0603"))
    )
    (comp (ref "R53")
      (value "100k")
      (footprint "eagle-import:R0603")
      (fields (field (name "PARTNO") "CRCW0603100KFKEAC"))
      (libsource (lib "eagle-import") (part "R-EU_R0603"))
    )
    (comp (ref "R54")
      (value "100k")
      (footprint "eagle-import:R0603")
      (fields (field (name "PARTNO") "CRCW0603100KFKEAC"))
      (libsource (lib "eagle-import") (part "R-EU_R0603"))
    )
    (comp (ref "TP1")
      (value "TPTP10R")
      (footprint "eagle-import:TP10R")
      (libsource (lib "eagle-import") (part "TPTP10R"))
    )
    (comp (ref "TP2")
      (value "TPTP10R")
      (footprint "eagle-import:TP10R")
      (libsource (lib "eagle-import") (part "TPTP10R"))
    )
    (comp (ref "TP3")
      (value "TPTP10R")
      (footprint "eagle-import:TP10R")
      (libsource (lib "eagle-import") (part "TPTP10R"))
    )
    (comp (ref "TP4")
      (value "TPTP10R")
      (footprint "eagle-import:TP10R")
      (libsource (lib "eagle-import") (part "TPTP10R"))
    )
    (comp (ref "TP11")
      (value "TPTP10R")
      (footprint "eagle-import:TP10R")
      (libsource (lib "eagle-import") (part "TPTP10R"))
    )
    (comp (ref "U$1")
      (value "TPS563249DDCR")
      (footprint "eagle-import:SOT23-6")
      (fields (field (name "PARTNO") "TPS563249DDCR "))
      (libsource (lib "eagle-import") (part "TPS5632149DDCR"))
    )
    (comp (ref "U$4")
      (value "TPS563249DDCR")
      (footprint "eagle-import:SOT23-6")
      (fields (field (name "PARTNO") "TPS563249DDCR "))
      (libsource (lib "eagle-import") (part "TPS5632149DDCR"))
    )
    (comp (ref "X1")
      (value "TB001-500-02BE")
      (footprint "eagle-import:W237-102")
      (fields (field (name "MPN") "237-102") (field (name "PARTNO") "TB001-500-02BE"))
      (libsource (lib "eagle-import") (part "W237-102"))
    )
    (comp (ref "C8")
      (value "10u")
      (footprint "eagle-import:C0603K")
      (fields (field (name "PARTNO") "GRM188R61A106KE69J"))
      (libsource (lib "eagle-import") (part "C-EUC0603K"))
    )
    (comp (ref "C16")
      (value "100n")
      (footprint "eagle-import:C0603K")
      (fields (field (name "PARTNO") "CC0603KRX7R8BB104"))
      (libsource (lib "eagle-import") (part "C-EUC0603K"))
    )
    (comp (ref "C24")
      (value "10u")
      (footprint "eagle-import:C0603K")
      (fields (field (name "PARTNO") "GRM188R61A106KE69J"))
      (libsource (lib "eagle-import") (part "C-EUC0603K"))
    )
    (comp (ref "C25")
      (value "10u")
      (footprint "eagle-import:C0603K")
      (fields (field (name "PARTNO") "GRM188R61A106KE69J"))
      (libsource (lib "eagle-import") (part "C-EUC0603K"))
    )
    (comp (ref "C29")
      (value "DNI")
      (footprint "eagle-import:C0402")
      (fields (field (name "PARTNO") "C0402C220J5GAC7411"))
      (libsource (lib "eagle-import") (part "C-EUC0402"))
    )
    (comp (ref "C30")
      (value "DNI")
      (footprint "eagle-import:C0402")
      (fields (field (name "PARTNO") "C0402C220J5GAC7411"))
      (libsource (lib "eagle-import") (part "C-EUC0402"))
    )
    (comp (ref "C38")
      (value "100n")
      (footprint "eagle-import:C0603K")
      (fields (field (name "PARTNO") "CC0603KRX7R8BB104"))
      (libsource (lib "eagle-import") (part "C-EUC0603K"))
    )
    (comp (ref "C39")
      (value "10u")
      (footprint "eagle-import:C0603K")
      (fields (field (name "PARTNO") "GRM188R61A106KE69J"))
      (libsource (lib "eagle-import") (part "C-EUC0603K"))
    )
    (comp (ref "C40")
      (value "100n")
      (footprint "eagle-import:C0603K")
      (fields (field (name "PARTNO") "CC0603KRX7R8BB104"))
      (libsource (lib "eagle-import") (part "C-EUC0603K"))
    )
    (comp (ref "D6")
      (value "PESD1CANSC70")
      (footprint "eagle-import:SOT323-R")
      (fields (field (name "PARTNO") "PESD1CAN-UX"))
      (libsource (lib "eagle-import") (part "PESD1CANSC70"))
    )
    (comp (ref "FAN_5V")
      (value "2pin")
      (footprint "eagle-import:1X02")
      (fields (field (name "PARTNO") "TSW-102-07-G-S"))
      (libsource (lib "eagle-import") (part "PINHD-1X2"))
    )
    (comp (ref "J2")
      (value "ETH_CONN")
      (footprint "eagle-import:2X6")
      (fields (field (name "PARTNO") "CES-106-01-T-D"))
      (libsource (lib "eagle-import") (part "CONN_06X2PTH_FEMALE"))
    )
    (comp (ref "J4")
      (value "DNI")
      (footprint "eagle-import:SDCMF-10915W010")
      (fields (field (name "PARTNO") "GSD090012SEU"))
      (libsource (lib "eagle-import") (part "SDCARD"))
    )
    (comp (ref "J8")
      (value "1140084168")
      (footprint "eagle-import:1140084168")
      (fields (field (name "MOUSER_PART_NUMBER") "523-114-00841-68"))
      (libsource (lib "eagle-import") (part "1140084168"))
    )
    (comp (ref "JTAG1")
      (value "DNI")
      (footprint "eagle-import:2X05_1.27MM_SMT")
      (fields (field (name "PARTNO") "M50-3600542R"))
      (libsource (lib "eagle-import") (part "JTAG-CORTEXM3"))
    )
    (comp (ref "LED_HDR")
      (value "2pin")
      (footprint "eagle-import:1X02")
      (fields (field (name "PARTNO") "TSW-102-07-G-S"))
      (libsource (lib "eagle-import") (part "PINHD-1X2"))
    )
    (comp (ref "Q3")
      (value "Si2300DS")
      (footprint "eagle-import:SOT23")
      (fields (field (name "PARTNO") "SI2300DS-T1-GE3"))
      (libsource (lib "eagle-import") (part "MOSFET-NREFLOW"))
    )
    (comp (ref "R7")
      (value "0")
      (footprint "eagle-import:R0603")
      (fields (field (name "PARTNO") "CRCW06030000Z0EAC"))
      (libsource (lib "eagle-import") (part "R-EU_R0603"))
    )
    (comp (ref "R8")
      (value "0")
      (footprint "eagle-import:R0603")
      (fields (field (name "PARTNO") "CRCW06030000Z0EAC"))
      (libsource (lib "eagle-import") (part "R-EU_R0603"))
    )
    (comp (ref "R9")
      (value "100k")
      (footprint "eagle-import:R0603")
      (fields (field (name "PARTNO") "CRCW0603100KFKEAC"))
      (libsource (lib "eagle-import") (part "R-EU_R0603"))
    )
    (comp (ref "R10")
      (value "100")
      (footprint "eagle-import:R0603")
      (fields (field (name "PARTNO") "CRCW0603100RFKEAC"))
      (libsource (lib "eagle-import") (part "R-EU_R0603"))
    )
    (comp (ref "R12")
      (value "100")
      (footprint "eagle-import:R0603")
      (fields (field (name "PARTNO") "CRCW0603100RFKEAC"))
      (libsource (lib "eagle-import") (part "R-EU_R0603"))
    )
    (comp (ref "R13")
      (value "100")
      (footprint "eagle-import:R0603")
      (fields (field (name "PARTNO") "CRCW0603100RFKEAC"))
      (libsource (lib "eagle-import") (part "R-EU_R0603"))
    )
    (comp (ref "R14")
      (value "DNI")
      (footprint "eagle-import:R0603")
      (fields (field (name "PARTNO") "CRCW06030000Z0EAC"))
      (libsource (lib "eagle-import") (part "R-EU_R0603"))
    )
    (comp (ref "R17")
      (value "47")
      (footprint "eagle-import:R0603")
      (fields (field (name "PARTNO") "CRCW060347R0FKEAC"))
      (libsource (lib "eagle-import") (part "R-EU_R0603"))
    )
    (comp (ref "R19")
      (value "100")
      (footprint "eagle-import:R0603")
      (fields (field (name "PARTNO") "CRCW0603100RFKEAC"))
      (libsource (lib "eagle-import") (part "R-EU_R0603"))
    )
    (comp (ref "R20")
      (value "47")
      (footprint "eagle-import:R0603")
      (fields (field (name "PARTNO") "CRCW060347R0FKEAC"))
      (libsource (lib "eagle-import") (part "R-EU_R0603"))
    )
    (comp (ref "R21")
      (value "100k")
      (footprint "eagle-import:R0603")
      (fields (field (name "PARTNO") "CRCW0603100KFKEAC"))
      (libsource (lib "eagle-import") (part "R-EU_R0603"))
    )
    (comp (ref "R23")
      (value "DNI")
      (footprint "eagle-import:R0603")
      (fields (field (name "PARTNO") "CRCW06030000Z0EAC"))
      (libsource (lib "eagle-import") (part "R-EU_R0603"))
    )
    (comp (ref "R24")
      (value "100")
      (footprint "eagle-import:R0603")
      (fields (field (name "PARTNO") "CRCW0603100RFKEAC"))
      (libsource (lib "eagle-import") (part "R-EU_R0603"))
    )
    (comp (ref "R25")
      (value "10k")
      (footprint "eagle-import:R0603")
      (fields (field (name "PARTNO") "CRCW060310K0JNEAC"))
      (libsource (lib "eagle-import") (part "R-EU_R0603"))
    )
    (comp (ref "R31")
      (value "47")
      (footprint "eagle-import:R0603")
      (fields (field (name "PARTNO") "CRCW060347R0FKEAC"))
      (libsource (lib "eagle-import") (part "R-EU_R0603"))
    )
    (comp (ref "R32")
      (value "0")
      (footprint "eagle-import:R0603")
      (fields (field (name "PARTNO") "CRCW06030000Z0EAC"))
      (libsource (lib "eagle-import") (part "R-EU_R0603"))
    )
    (comp (ref "R37")
      (value "DNI")
      (footprint "eagle-import:R0603")
      (fields (field (name "PARTNO") "CRCW06030000Z0EAC"))
      (libsource (lib "eagle-import") (part "R-EU_R0603"))
    )
    (comp (ref "R47")
      (value "0")
      (footprint "eagle-import:R0603")
      (fields (field (name "PARTNO") "CRCW06030000Z0EAC"))
      (libsource (lib "eagle-import") (part "R-EU_R0603"))
    )
    (comp (ref "R48")
      (value "47")
      (footprint "eagle-import:R0603")
      (fields (field (name "PARTNO") "CRCW060347R0FKEAC"))
      (libsource (lib "eagle-import") (part "R-EU_R0603"))
    )
    (comp (ref "R55")
      (value "47")
      (footprint "eagle-import:R0603")
      (fields (field (name "PARTNO") "CRCW060347R0FKEAC"))
      (libsource (lib "eagle-import") (part "R-EU_R0603"))
    )
    (comp (ref "R63")
      (value "47")
      (footprint "eagle-import:R0603")
      (fields (field (name "PARTNO") "CRCW060347R0FKEAC"))
      (libsource (lib "eagle-import") (part "R-EU_R0603"))
    )
    (comp (ref "R64")
      (value "10k")
      (footprint "eagle-import:R0603")
      (fields (field (name "PARTNO") "CRCW060310K0JNEAC"))
      (libsource (lib "eagle-import") (part "R-EU_R0603"))
    )
    (comp (ref "R65")
      (value "0")
      (footprint "eagle-import:R0603")
      (fields (field (name "PARTNO") "CRCW06030000Z0EAC"))
      (libsource (lib "eagle-import") (part "R-EU_R0603"))
    )
    (comp (ref "R68")
      (value "10k")
      (footprint "eagle-import:R0603")
      (fields (field (name "PARTNO") "CRCW060310K0JNEAC"))
      (libsource (lib "eagle-import") (part "R-EU_R0603"))
    )
    (comp (ref "S1")
      (value "31-XX")
      (footprint "eagle-import:B3F-31XX")
      (fields (field (name "PARTNO") "FSMRA5JH"))
      (libsource (lib "eagle-import") (part "31-XX"))
    )
    (comp (ref "TP5")
      (value "TPTP10R")
      (footprint "eagle-import:TP10R")
      (libsource (lib "eagle-import") (part "TPTP10R"))
    )
    (comp (ref "TP6")
      (value "TPTP10R")
      (footprint "eagle-import:TP10R")
      (libsource (lib "eagle-import") (part "TPTP10R"))
    )
    (comp (ref "TP7")
      (value "TPTP10R")
      (footprint "eagle-import:TP10R")
      (libsource (lib "eagle-import") (part "TPTP10R"))
    )
    (comp (ref "TP8")
      (value "TPTP10R")
      (footprint "eagle-import:TP10R")
      (libsource (lib "eagle-import") (part "TPTP10R"))
    )
    (comp (ref "TP9")
      (value "TPTP10R")
      (footprint "eagle-import:TP10R")
      (libsource (lib "eagle-import") (part "TPTP10R"))
    )
    (comp (ref "TP19")
      (value "TPTP10R")
      (footprint "eagle-import:TP10R")
      (libsource (lib "eagle-import") (part "TPTP10R"))
    )
    (comp (ref "TP20")
      (value "TPTP10R")
      (footprint "eagle-import:TP10R")
      (libsource (lib "eagle-import") (part "TPTP10R"))
    )
    (comp (ref "U$2")
      (value "DNI")
      (footprint "eagle-import:2X03_1.27MM_SMT")
      (fields (field (name "PARTNO") "HTMS-103-03-T-D-SM"))
      (libsource (lib "eagle-import") (part "HEADER_3X6P_ESPPROG"))
    )
    (comp (ref "U$7")
      (value "ETH_MODULE_OUTLINE")
      (footprint "eagle-import:ETH_MODULE_OUTLINE_SMALL")
      (libsource (lib "eagle-import") (part "ETH_MODULE_OUTLINE"))
    )
    (comp (ref "U2")
      (value "ESP-WROOM-32E-VARIANT-GNDCHANGE")
      (footprint "eagle-import:ESP-WROOM-32E")
      (fields (field (name "PARTNO") "ESP32-WROOM-32"))
      (libsource (lib "eagle-import") (part "ESP-WROOM-32E-VARIANT-GNDCHANGE"))
    )
    (comp (ref "Y3")
      (value "DNI")
      (footprint "eagle-import:CRYSTAL-SMD-3.2X1.5MM")
      (fields (field (name "PARTNO") "FC-135 32.7680KA-A3"))
      (libsource (lib "eagle-import") (part "CRYSTAL-32.768KHZSMD-3.2X1.5"))
    )
    (comp (ref "Q5")
      (value "FDN306P")
      (footprint "eagle-import:SOT23-WIDE")
      (libsource (lib "eagle-import") (part "MOSFET-PWIDE"))
    )
    (comp (ref "Q6")
      (value "FDN306P")
      (footprint "eagle-import:SOT23-WIDE")
      (libsource (lib "eagle-import") (part "MOSFET-PWIDE"))
    )
    (comp (ref "Q8")
      (value "FDN306P")
      (footprint "eagle-import:SOT23-WIDE")
      (libsource (lib "eagle-import") (part "MOSFET-PWIDE"))
    )
    (comp (ref "Q9")
      (value "FDN306P")
      (footprint "eagle-import:SOT23-WIDE")
      (libsource (lib "eagle-import") (part "MOSFET-PWIDE"))
    )
    (comp (ref "Q10")
      (value "FDN306P")
      (footprint "eagle-import:SOT23-WIDE")
      (libsource (lib "eagle-import") (part "MOSFET-PWIDE"))
    )
    (comp (ref "Q11")
      (value "FDN306P")
      (footprint "eagle-import:SOT23-WIDE")
      (libsource (lib "eagle-import") (part "MOSFET-PWIDE"))
    )
    (comp (ref "Q12")
      (value "FDN306P")
      (footprint "eagle-import:SOT23-WIDE")
      (libsource (lib "eagle-import") (part "MOSFET-PWIDE"))
    )
    (comp (ref "Q13")
      (value "FDN306P")
      (footprint "eagle-import:SOT23-WIDE")
      (libsource (lib "eagle-import") (part "MOSFET-PWIDE"))
    )
    (comp (ref "Q14")
      (value "FDN306P")
      (footprint "eagle-import:SOT23-WIDE")
      (libsource (lib "eagle-import") (part "MOSFET-PWIDE"))
    )
    (comp (ref "Q15")
      (value "FDN306P")
      (footprint "eagle-import:SOT23-WIDE")
      (libsource (lib "eagle-import") (part "MOSFET-PWIDE"))
    )
    (comp (ref "R67")
      (value "10k")
      (footprint "eagle-import:R0603")
      (fields (field (name "PARTNO") "CRCW060310K0JNEAC"))
      (libsource (lib "eagle-import") (part "R-EU_R0603"))
    )
    (comp (ref "R70")
      (value "10k")
      (footprint "eagle-import:R0603")
      (fields (field (name "PARTNO") "CRCW060310K0JNEAC"))
      (libsource (lib "eagle-import") (part "R-EU_R0603"))
    )
    (comp (ref "R71")
      (value "10k")
      (footprint "eagle-import:R0603")
      (fields (field (name "PARTNO") "CRCW060310K0JNEAC"))
      (libsource (lib "eagle-import") (part "R-EU_R0603"))
    )
    (comp (ref "R72")
      (value "10k")
      (footprint "eagle-import:R0603")
      (fields (field (name "PARTNO") "CRCW060310K0JNEAC"))
      (libsource (lib "eagle-import") (part "R-EU_R0603"))
    )
    (comp (ref "R73")
      (value "10k")
      (footprint "eagle-import:R0603")
      (fields (field (name "PARTNO") "CRCW060310K0JNEAC"))
      (libsource (lib "eagle-import") (part "R-EU_R0603"))
    )
    (comp (ref "R74")
      (value "10k")
      (footprint "eagle-import:R0603")
      (fields (field (name "PARTNO") "CRCW060310K0JNEAC"))
      (libsource (lib "eagle-import") (part "R-EU_R0603"))
    )
    (comp (ref "R75")
      (value "10k")
      (footprint "eagle-import:R0603")
      (fields (field (name "PARTNO") "CRCW060310K0JNEAC"))
      (libsource (lib "eagle-import") (part "R-EU_R0603"))
    )
    (comp (ref "R76")
      (value "10k")
      (footprint "eagle-import:R0603")
      (fields (field (name "PARTNO") "CRCW060310K0JNEAC"))
      (libsource (lib "eagle-import") (part "R-EU_R0603"))
    )
    (comp (ref "R77")
      (value "10k")
      (footprint "eagle-import:R0603")
      (fields (field (name "PARTNO") "CRCW060310K0JNEAC"))
      (libsource (lib "eagle-import") (part "R-EU_R0603"))
    )
    (comp (ref "R78")
      (value "10k")
      (footprint "eagle-import:R0603")
      (fields (field (name "PARTNO") "CRCW060310K0JNEAC"))
      (libsource (lib "eagle-import") (part "R-EU_R0603"))
    )
    (comp (ref "U$3")
      (value "CONN_03X2_WE_61200621621")
      (footprint "eagle-import:WE_61200621621")
      (fields (field (name "PARTNO") "61200621621"))
      (libsource (lib "eagle-import") (part "CONN_03X2_WE_61200621621"))
    )
    (comp (ref "U$8")
      (value "CONN_03X2_WE_61200621621")
      (footprint "eagle-import:WE_61200621621")
      (fields (field (name "PARTNO") "61200621621"))
      (libsource (lib "eagle-import") (part "CONN_03X2_WE_61200621621"))
    )
    (comp (ref "U$9")
      (value "CONN_03X2_WE_61200621621")
      (footprint "eagle-import:WE_61200621621")
      (fields (field (name "PARTNO") "61200621621"))
      (libsource (lib "eagle-import") (part "CONN_03X2_WE_61200621621"))
    )
    (comp (ref "U$10")
      (value "CONN_03X2_WE_61200621621")
      (footprint "eagle-import:WE_61200621621")
      (fields (field (name "PARTNO") "61200621621"))
      (libsource (lib "eagle-import") (part "CONN_03X2_WE_61200621621"))
    )
    (comp (ref "U$11")
      (value "CONN_03X2_WE_61200621621")
      (footprint "eagle-import:WE_61200621621")
      (fields (field (name "PARTNO") "61200621621"))
      (libsource (lib "eagle-import") (part "CONN_03X2_WE_61200621621"))
    )
    (comp (ref "U$12")
      (value "CONN_03X2_WE_61200621621")
      (footprint "eagle-import:WE_61200621621")
      (fields (field (name "PARTNO") "61200621621"))
      (libsource (lib "eagle-import") (part "CONN_03X2_WE_61200621621"))
    )
    (comp (ref "U$13")
      (value "CONN_03X2_WE_61200621621")
      (footprint "eagle-import:WE_61200621621")
      (fields (field (name "PARTNO") "61200621621"))
      (libsource (lib "eagle-import") (part "CONN_03X2_WE_61200621621"))
    )
    (comp (ref "U$14")
      (value "CONN_03X2_WE_61200621621")
      (footprint "eagle-import:WE_61200621621")
      (fields (field (name "PARTNO") "61200621621"))
      (libsource (lib "eagle-import") (part "CONN_03X2_WE_61200621621"))
    )
    (comp (ref "U$15")
      (value "CONN_03X2_WE_61200621621")
      (footprint "eagle-import:WE_61200621621")
      (fields (field (name "PARTNO") "61200621621"))
      (libsource (lib "eagle-import") (part "CONN_03X2_WE_61200621621"))
    )
    (comp (ref "U$16")
      (value "CONN_03X2_WE_61200621621")
      (footprint "eagle-import:WE_61200621621")
      (fields (field (name "PARTNO") "61200621621"))
      (libsource (lib "eagle-import") (part "CONN_03X2_WE_61200621621"))
    )
  )
  (nets
    (net (code "1") (name "+5V{slash}1") (class "Default")
      (node (ref "C20") (pin "1") (pinfunction "1_1") (pintype "passive"))
      (node (ref "C22") (pin "1") (pinfunction "1_1") (pintype "passive"))
      (node (ref "C32") (pin "1") (pinfunction "1_1") (pintype "passive"))
      (node (ref "C4") (pin "1") (pinfunction "1_1") (pintype "passive"))
      (node (ref "C42") (pin "1") (pinfunction "1_1") (pintype "passive"))
      (node (ref "C44") (pin "1") (pinfunction "1_1") (pintype "passive"))
      (node (ref "C45") (pin "1") (pinfunction "1_1") (pintype "passive"))
      (node (ref "FB1") (pin "2") (pinfunction "P$2_2") (pintype "passive"))
      (node (ref "FB9") (pin "2") (pinfunction "P$2_2") (pintype "passive"))
      (node (ref "IC2") (pin "8") (pinfunction "VDD_8") (pintype "bidirectional"))
      (node (ref "IC3") (pin "8") (pinfunction "VCC_8") (pintype "power_in"))
      (node (ref "IC4") (pin "1") (pinfunction "ADDR_1") (pintype "bidirectional"))
      (node (ref "IC4") (pin "8") (pinfunction "VDD_8") (pintype "bidirectional"))
      (node (ref "IC5") (pin "8") (pinfunction "VDD_8") (pintype "bidirectional"))
      (node (ref "IC8") (pin "24") (pinfunction "24_VDD_24") (pintype "power_in"))
      (node (ref "J9") (pin "4") (pinfunction "4_4") (pintype "passive"))
      (node (ref "Q10") (pin "2") (pinfunction "S_2") (pintype "passive"))
      (node (ref "Q11") (pin "2") (pinfunction "S_2") (pintype "passive"))
      (node (ref "Q12") (pin "2") (pinfunction "S_2") (pintype "passive"))
      (node (ref "Q13") (pin "2") (pinfunction "S_2") (pintype "passive"))
      (node (ref "Q14") (pin "2") (pinfunction "S_2") (pintype "passive"))
      (node (ref "Q15") (pin "2") (pinfunction "S_2") (pintype "passive"))
      (node (ref "Q5") (pin "2") (pinfunction "S_2") (pintype "passive"))
      (node (ref "Q6") (pin "2") (pinfunction "S_2") (pintype "passive"))
      (node (ref "Q8") (pin "2") (pinfunction "S_2") (pintype "passive"))
      (node (ref "Q9") (pin "2") (pinfunction "S_2") (pintype "passive"))
      (node (ref "R33") (pin "1") (pinfunction "1_1") (pintype "passive"))
      (node (ref "R34") (pin "1") (pinfunction "1_1") (pintype "passive"))
      (node (ref "R36") (pin "1") (pinfunction "1_1") (pintype "passive"))
      (node (ref "R67") (pin "1") (pinfunction "1_1") (pintype "passive"))
      (node (ref "R70") (pin "1") (pinfunction "1_1") (pintype "passive"))
      (node (ref "R71") (pin "1") (pinfunction "1_1") (pintype "passive"))
      (node (ref "R72") (pin "1") (pinfunction "1_1") (pintype "passive"))
      (node (ref "R73") (pin "1") (pinfunction "1_1") (pintype "passive"))
      (node (ref "R74") (pin "1") (pinfunction "1_1") (pintype "passive"))
      (node (ref "R75") (pin "1") (pinfunction "1_1") (pintype "passive"))
      (node (ref "R76") (pin "1") (pinfunction "1_1") (pintype "passive"))
      (node (ref "R77") (pin "1") (pinfunction "1_1") (pintype "passive"))
      (node (ref "R78") (pin "1") (pinfunction "1_1") (pintype "passive"))
      (node (ref "R81") (pin "1") (pinfunction "1_1") (pintype "passive"))
      (node (ref "R82") (pin "1") (pinfunction "1_1") (pintype "passive"))
      (node (ref "U1") (pin "8") (pinfunction "VCC(B)_8") (pintype "power_in"))
    )
    (net (code "2") (name "1AIN0") (class "Default")
      (node (ref "C21") (pin "1") (pinfunction "1_1") (pintype "passive"))
      (node (ref "IC5") (pin "6") (pinfunction "AIN2_6") (pintype "bidirectional"))
      (node (ref "R83") (pin "1") (pinfunction "1_1") (pintype "passive"))
    )
    (net (code "3") (name "1AIN1") (class "Default")
      (node (ref "C46") (pin "1") (pinfunction "1_1") (pintype "passive"))
      (node (ref "IC5") (pin "7") (pinfunction "AIN3_7") (pintype "bidirectional"))
      (node (ref "R84") (pin "1") (pinfunction "1_1") (pintype "passive"))
    )
    (net (code "4") (name "1AIN2") (class "Default")
      (node (ref "C47") (pin "1") (pinfunction "1_1") (pintype "passive"))
      (node (ref "IC5") (pin "5") (pinfunction "AIN1_5") (pintype "bidirectional"))
      (node (ref "R85") (pin "1") (pinfunction "1_1") (pintype "passive"))
    )
    (net (code "5") (name "1AIN3") (class "Default")
      (node (ref "C48") (pin "1") (pinfunction "1_1") (pintype "passive"))
      (node (ref "IC5") (pin "4") (pinfunction "AIN0_4") (pintype "bidirectional"))
      (node (ref "R86") (pin "1") (pinfunction "1_1") (pintype "passive"))
    )
    (net (code "6") (name "2AIN0") (class "Default")
      (node (ref "C49") (pin "1") (pinfunction "1_1") (pintype "passive"))
      (node (ref "IC4") (pin "6") (pinfunction "AIN2_6") (pintype "bidirectional"))
      (node (ref "R87") (pin "1") (pinfunction "1_1") (pintype "passive"))
    )
    (net (code "7") (name "2AIN1") (class "Default")
      (node (ref "C50") (pin "1") (pinfunction "1_1") (pintype "passive"))
      (node (ref "IC4") (pin "7") (pinfunction "AIN3_7") (pintype "bidirectional"))
      (node (ref "R88") (pin "1") (pinfunction "1_1") (pintype "passive"))
    )
    (net (code "8") (name "2AIN2") (class "Default")
      (node (ref "C51") (pin "1") (pinfunction "1_1") (pintype "passive"))
      (node (ref "IC4") (pin "5") (pinfunction "AIN1_5") (pintype "bidirectional"))
      (node (ref "R89") (pin "1") (pinfunction "1_1") (pintype "passive"))
    )
    (net (code "9") (name "2AIN3") (class "Default")
      (node (ref "C52") (pin "1") (pinfunction "1_1") (pintype "passive"))
      (node (ref "IC4") (pin "4") (pinfunction "AIN0_4") (pintype "bidirectional"))
      (node (ref "R90") (pin "1") (pinfunction "1_1") (pintype "passive"))
    )
    (net (code "10") (name "3.3V") (class "Default")
      (node (ref "C10") (pin "1") (pinfunction "1_1") (pintype "passive"))
      (node (ref "C11") (pin "1") (pinfunction "1_1") (pintype "passive"))
      (node (ref "C12") (pin "1") (pinfunction "1_1") (pintype "passive"))
      (node (ref "C2") (pin "1") (pinfunction "1_1") (pintype "passive"))
      (node (ref "C24") (pin "1") (pinfunction "1_1") (pintype "passive"))
      (node (ref "C25") (pin "1") (pinfunction "1_1") (pintype "passive"))
      (node (ref "C3") (pin "1") (pinfunction "1_1") (pintype "passive"))
      (node (ref "C39") (pin "1") (pinfunction "1_1") (pintype "passive"))
      (node (ref "C40") (pin "1") (pinfunction "1_1") (pintype "passive"))
      (node (ref "C43") (pin "1") (pinfunction "1_1") (pintype "passive"))
      (node (ref "D6") (pin "3") (pinfunction "3_3") (pintype "passive"))
      (node (ref "IC1") (pin "6") (pinfunction "VDD_6") (pintype "power_in"))
      (node (ref "IC1") (pin "7") (pinfunction "REGIN_7") (pintype "passive"))
      (node (ref "J2") (pin "2") (pinfunction "2_2") (pintype "passive"))
      (node (ref "L2") (pin "P$2") (pinfunction "2_P$2") (pintype "passive"))
      (node (ref "R19") (pin "2") (pinfunction "2_2") (pintype "passive"))
      (node (ref "R23") (pin "1") (pinfunction "1_1") (pintype "passive"))
      (node (ref "R25") (pin "2") (pinfunction "2_2") (pintype "passive"))
      (node (ref "R26") (pin "1") (pinfunction "1_1") (pintype "passive"))
      (node (ref "R27") (pin "1") (pinfunction "1_1") (pintype "passive"))
      (node (ref "R29") (pin "2") (pinfunction "2_2") (pintype "passive"))
      (node (ref "R30") (pin "2") (pinfunction "2_2") (pintype "passive"))
      (node (ref "R42") (pin "1") (pinfunction "1_1") (pintype "passive"))
      (node (ref "R64") (pin "2") (pinfunction "2_2") (pintype "passive"))
      (node (ref "R65") (pin "2") (pinfunction "2_2") (pintype "passive"))
      (node (ref "R68") (pin "2") (pinfunction "2_2") (pintype "passive"))
      (node (ref "R7") (pin "1") (pinfunction "1_1") (pintype "passive"))
      (node (ref "R8") (pin "2") (pinfunction "2_2") (pintype "passive"))
      (node (ref "TP2") (pin "TP") (pinfunction "TP_TP") (pintype "input"))
      (node (ref "U1") (pin "1") (pinfunction "VCC(A)_1") (pintype "power_in"))
      (node (ref "U1") (pin "5") (pinfunction "EN_5") (pintype "input"))
      (node (ref "U2") (pin "2") (pinfunction "3V3_2") (pintype "bidirectional"))
    )
    (net (code "11") (name "3AIN0") (class "Default")
      (node (ref "C18") (pin "1") (pinfunction "1_1") (pintype "passive"))
      (node (ref "IC2") (pin "5") (pinfunction "AIN1_5") (pintype "bidirectional"))
      (node (ref "R15") (pin "1") (pinfunction "1_1") (pintype "passive"))
    )
    (net (code "12") (name "3AIN1") (class "Default")
      (node (ref "C19") (pin "1") (pinfunction "1_1") (pintype "passive"))
      (node (ref "IC2") (pin "6") (pinfunction "AIN2_6") (pintype "bidirectional"))
      (node (ref "R18") (pin "1") (pinfunction "1_1") (pintype "passive"))
    )
    (net (code "13") (name "5V") (class "Default")
      (node (ref "C17") (pin "1") (pinfunction "1_1") (pintype "passive"))
      (node (ref "C26") (pin "1") (pinfunction "1_1") (pintype "passive"))
      (node (ref "C27") (pin "1") (pinfunction "1_1") (pintype "passive"))
      (node (ref "C8") (pin "1") (pinfunction "1_1") (pintype "passive"))
      (node (ref "FAN_5V") (pin "2") (pinfunction "2_2") (pintype "passive"))
      (node (ref "FB1") (pin "1") (pinfunction "P$1_1") (pintype "passive"))
      (node (ref "FB9") (pin "1") (pinfunction "P$1_1") (pintype "passive"))
      (node (ref "L3") (pin "P$2") (pinfunction "2_P$2") (pintype "passive"))
      (node (ref "R37") (pin "2") (pinfunction "2_2") (pintype "passive"))
      (node (ref "R51") (pin "2") (pinfunction "2_2") (pintype "passive"))
      (node (ref "R52") (pin "2") (pinfunction "2_2") (pintype "passive"))
      (node (ref "TP3") (pin "TP") (pinfunction "TP_TP") (pintype "input"))
    )
    (net (code "14") (name "5V_CALM") (class "Default")
      (node (ref "FB7") (pin "2") (pinfunction "P$2_2") (pintype "passive"))
      (node (ref "U$10") (pin "3") (pinfunction "3_3") (pintype "bidirectional"))
      (node (ref "U$11") (pin "3") (pinfunction "3_3") (pintype "bidirectional"))
      (node (ref "U$12") (pin "3") (pinfunction "3_3") (pintype "bidirectional"))
      (node (ref "U$13") (pin "3") (pinfunction "3_3") (pintype "bidirectional"))
      (node (ref "U$14") (pin "3") (pinfunction "3_3") (pintype "bidirectional"))
      (node (ref "U$15") (pin "3") (pinfunction "3_3") (pintype "bidirectional"))
      (node (ref "U$16") (pin "3") (pinfunction "3_3") (pintype "bidirectional"))
      (node (ref "U$3") (pin "3") (pinfunction "3_3") (pintype "bidirectional"))
      (node (ref "U$8") (pin "3") (pinfunction "3_3") (pintype "bidirectional"))
      (node (ref "U$9") (pin "3") (pinfunction "3_3") (pintype "bidirectional"))
    )
    (net (code "15") (name "5V_CALM_LDO") (class "Default")
      (node (ref "C41") (pin "1") (pinfunction "1_1") (pintype "passive"))
      (node (ref "FB7") (pin "1") (pinfunction "P$1_1") (pintype "passive"))
      (node (ref "IC9") (pin "3") (pinfunction "3_VOUT_3") (pintype "bidirectional"))
    )
    (net (code "16") (name "ACTIVE") (class "Default")
      (node (ref "IC1") (pin "11") (pinfunction "~{SUSPEND}_11") (pintype "output"))
      (node (ref "R40") (pin "2") (pinfunction "2_2") (pintype "passive"))
    )
    (net (code "17") (name "ADC1_1") (class "Default")
      (node (ref "R83") (pin "2") (pinfunction "2_2") (pintype "passive"))
      (node (ref "U$3") (pin "2") (pinfunction "2_2") (pintype "bidirectional"))
    )
    (net (code "18") (name "ADC1_2") (class "Default")
      (node (ref "R84") (pin "2") (pinfunction "2_2") (pintype "passive"))
      (node (ref "U$8") (pin "2") (pinfunction "2_2") (pintype "bidirectional"))
    )
    (net (code "19") (name "ADC1_3") (class "Default")
      (node (ref "R85") (pin "2") (pinfunction "2_2") (pintype "passive"))
      (node (ref "U$9") (pin "2") (pinfunction "2_2") (pintype "bidirectional"))
    )
    (net (code "20") (name "ADC1_4") (class "Default")
      (node (ref "R86") (pin "2") (pinfunction "2_2") (pintype "passive"))
      (node (ref "U$10") (pin "2") (pinfunction "2_2") (pintype "bidirectional"))
    )
    (net (code "21") (name "ADC2_1") (class "Default")
      (node (ref "R87") (pin "2") (pinfunction "2_2") (pintype "passive"))
      (node (ref "U$11") (pin "2") (pinfunction "2_2") (pintype "bidirectional"))
    )
    (net (code "22") (name "ADC2_2") (class "Default")
      (node (ref "R88") (pin "2") (pinfunction "2_2") (pintype "passive"))
      (node (ref "U$12") (pin "2") (pinfunction "2_2") (pintype "bidirectional"))
    )
    (net (code "23") (name "ADC2_3") (class "Default")
      (node (ref "R89") (pin "2") (pinfunction "2_2") (pintype "passive"))
      (node (ref "U$13") (pin "2") (pinfunction "2_2") (pintype "bidirectional"))
    )
    (net (code "24") (name "ADC2_4") (class "Default")
      (node (ref "R90") (pin "2") (pinfunction "2_2") (pintype "passive"))
      (node (ref "U$14") (pin "2") (pinfunction "2_2") (pintype "bidirectional"))
    )
    (net (code "25") (name "ADC3_1") (class "Default")
      (node (ref "R15") (pin "2") (pinfunction "2_2") (pintype "passive"))
      (node (ref "U$15") (pin "2") (pinfunction "2_2") (pintype "bidirectional"))
    )
    (net (code "26") (name "ADC3_2") (class "Default")
      (node (ref "R18") (pin "2") (pinfunction "2_2") (pintype "passive"))
      (node (ref "U$16") (pin "2") (pinfunction "2_2") (pintype "bidirectional"))
    )
    (net (code "27") (name "AGND") (class "Default")
      (node (ref "C18") (pin "2") (pinfunction "2_2") (pintype "passive"))
      (node (ref "C19") (pin "2") (pinfunction "2_2") (pintype "passive"))
      (node (ref "C20") (pin "2") (pinfunction "2_2") (pintype "passive"))
      (node (ref "C21") (pin "2") (pinfunction "2_2") (pintype "passive"))
      (node (ref "C22") (pin "2") (pinfunction "2_2") (pintype "passive"))
      (node (ref "C32") (pin "2") (pinfunction "2_2") (pintype "passive"))
      (node (ref "C4") (pin "2") (pinfunction "2_2") (pintype "passive"))
      (node (ref "C44") (pin "2") (pinfunction "2_2") (pintype "passive"))
      (node (ref "C45") (pin "2") (pinfunction "2_2") (pintype "passive"))
      (node (ref "C46") (pin "2") (pinfunction "2_2") (pintype "passive"))
      (node (ref "C47") (pin "2") (pinfunction "2_2") (pintype "passive"))
      (node (ref "C48") (pin "2") (pinfunction "2_2") (pintype "passive"))
      (node (ref "C49") (pin "2") (pinfunction "2_2") (pintype "passive"))
      (node (ref "C50") (pin "2") (pinfunction "2_2") (pintype "passive"))
      (node (ref "C51") (pin "2") (pinfunction "2_2") (pintype "passive"))
      (node (ref "C52") (pin "2") (pinfunction "2_2") (pintype "passive"))
      (node (ref "FB2") (pin "2") (pinfunction "P$2_2") (pintype "passive"))
      (node (ref "FB8") (pin "2") (pinfunction "P$2_2") (pintype "passive"))
      (node (ref "IC2") (pin "3") (pinfunction "GND_3") (pintype "bidirectional"))
      (node (ref "IC3") (pin "4") (pinfunction "GND_4") (pintype "power_in"))
      (node (ref "IC4") (pin "3") (pinfunction "GND_3") (pintype "bidirectional"))
      (node (ref "IC5") (pin "3") (pinfunction "GND_3") (pintype "bidirectional"))
      (node (ref "IC8") (pin "12") (pinfunction "VSS_12") (pintype "power_in"))
      (node (ref "IC8") (pin "2") (pinfunction "A1_2") (pintype "input"))
      (node (ref "IC8") (pin "21") (pinfunction "A0_21") (pintype "input"))
      (node (ref "J9") (pin "1") (pinfunction "1_1") (pintype "passive"))
      (node (ref "R35") (pin "2") (pinfunction "2_2") (pintype "passive"))
      (node (ref "U$10") (pin "1") (pinfunction "1_1") (pintype "bidirectional"))
      (node (ref "U$11") (pin "1") (pinfunction "1_1") (pintype "bidirectional"))
      (node (ref "U$12") (pin "1") (pinfunction "1_1") (pintype "bidirectional"))
      (node (ref "U$13") (pin "1") (pinfunction "1_1") (pintype "bidirectional"))
      (node (ref "U$14") (pin "1") (pinfunction "1_1") (pintype "bidirectional"))
      (node (ref "U$15") (pin "1") (pinfunction "1_1") (pintype "bidirectional"))
      (node (ref "U$16") (pin "1") (pinfunction "1_1") (pintype "bidirectional"))
      (node (ref "U$3") (pin "1") (pinfunction "1_1") (pintype "bidirectional"))
      (node (ref "U$8") (pin "1") (pinfunction "1_1") (pintype "bidirectional"))
      (node (ref "U$9") (pin "1") (pinfunction "1_1") (pintype "bidirectional"))
    )
    (net (code "28") (name "BTN1") (class "Default")
      (node (ref "R14") (pin "2") (pinfunction "2_2") (pintype "passive"))
      (node (ref "R68") (pin "1") (pinfunction "1_1") (pintype "passive"))
      (node (ref "S1") (pin "1") (pinfunction "P_1") (pintype "passive"))
      (node (ref "U2") (pin "6") (pinfunction "IO34_6") (pintype "bidirectional"))
    )
    (net (code "29") (name "DTR") (class "Default")
      (node (ref "IC1") (pin "28") (pinfunction "DTR_28") (pintype "output"))
      (node (ref "R1") (pin "2") (pinfunction "2_2") (pintype "passive"))
      (node (ref "T1") (pin "2") (pinfunction "E_2") (pintype "passive"))
    )
    (net (code "30") (name "D_N_") (class "Default")
      (node (ref "D1") (pin "3") (pinfunction "3_3") (pintype "passive"))
      (node (ref "J5") (pin "D-") (pinfunction "D-_D-") (pintype "bidirectional"))
      (node (ref "R6") (pin "1") (pinfunction "1_1") (pintype "passive"))
    )
    (net (code "31") (name "D_N_CP") (class "Default")
      (node (ref "IC1") (pin "5") (pinfunction "D-_5") (pintype "bidirectional"))
      (node (ref "R6") (pin "2") (pinfunction "2_2") (pintype "passive"))
    )
    (net (code "32") (name "D_P_") (class "Default")
      (node (ref "D2") (pin "3") (pinfunction "3_3") (pintype "passive"))
      (node (ref "J5") (pin "D+") (pinfunction "D+_D+") (pintype "bidirectional"))
      (node (ref "R5") (pin "1") (pinfunction "1_1") (pintype "passive"))
    )
    (net (code "33") (name "D_P_CP") (class "Default")
      (node (ref "IC1") (pin "4") (pinfunction "D+_4") (pintype "bidirectional"))
      (node (ref "R5") (pin "2") (pinfunction "2_2") (pintype "passive"))
    )
    (net (code "34") (name "ENB_PWR_IF1") (class "Default")
      (node (ref "IC8") (pin "10") (pinfunction "I/O0.6_10") (pintype "bidirectional"))
      (node (ref "Q5") (pin "1") (pinfunction "G_1") (pintype "passive"))
      (node (ref "R67") (pin "2") (pinfunction "2_2") (pintype "passive"))
    )
    (net (code "35") (name "ENB_PWR_IF2") (class "Default")
      (node (ref "IC8") (pin "11") (pinfunction "I/O0.7_11") (pintype "bidirectional"))
      (node (ref "Q6") (pin "1") (pinfunction "G_1") (pintype "passive"))
      (node (ref "R70") (pin "2") (pinfunction "2_2") (pintype "passive"))
    )
    (net (code "36") (name "ENB_PWR_IF3") (class "Default")
      (node (ref "IC8") (pin "6") (pinfunction "I/O0.2_6") (pintype "bidirectional"))
      (node (ref "Q8") (pin "1") (pinfunction "G_1") (pintype "passive"))
      (node (ref "R71") (pin "2") (pinfunction "2_2") (pintype "passive"))
    )
    (net (code "37") (name "ENB_PWR_IF4") (class "Default")
      (node (ref "IC8") (pin "7") (pinfunction "I/O0.3_7") (pintype "bidirectional"))
      (node (ref "Q9") (pin "1") (pinfunction "G_1") (pintype "passive"))
      (node (ref "R72") (pin "2") (pinfunction "2_2") (pintype "passive"))
    )
    (net (code "38") (name "ENB_PWR_IF5") (class "Default")
      (node (ref "IC8") (pin "8") (pinfunction "I/O0.4_8") (pintype "bidirectional"))
      (node (ref "Q10") (pin "1") (pinfunction "G_1") (pintype "passive"))
      (node (ref "R73") (pin "2") (pinfunction "2_2") (pintype "passive"))
    )
    (net (code "39") (name "ENB_PWR_IF6") (class "Default")
      (node (ref "IC8") (pin "9") (pinfunction "I/O0.5_9") (pintype "bidirectional"))
      (node (ref "Q11") (pin "1") (pinfunction "G_1") (pintype "passive"))
      (node (ref "R74") (pin "2") (pinfunction "2_2") (pintype "passive"))
    )
    (net (code "40") (name "ENB_PWR_IF7") (class "Default")
      (node (ref "IC8") (pin "20") (pinfunction "I/O1.7_20") (pintype "bidirectional"))
      (node (ref "Q12") (pin "1") (pinfunction "G_1") (pintype "passive"))
      (node (ref "R75") (pin "2") (pinfunction "2_2") (pintype "passive"))
    )
    (net (code "41") (name "ENB_PWR_IF8") (class "Default")
      (node (ref "IC8") (pin "19") (pinfunction "I/O1.6_19") (pintype "bidirectional"))
      (node (ref "Q13") (pin "1") (pinfunction "G_1") (pintype "passive"))
      (node (ref "R76") (pin "2") (pinfunction "2_2") (pintype "passive"))
    )
    (net (code "42") (name "ENB_PWR_IF9") (class "Default")
      (node (ref "IC8") (pin "5") (pinfunction "I/O0.1_5") (pintype "bidirectional"))
      (node (ref "Q14") (pin "1") (pinfunction "G_1") (pintype "passive"))
      (node (ref "R77") (pin "2") (pinfunction "2_2") (pintype "passive"))
    )
    (net (code "43") (name "ENB_PWR_IF10") (class "Default")
      (node (ref "IC8") (pin "4") (pinfunction "I/O0.0_4") (pintype "bidirectional"))
      (node (ref "Q15") (pin "1") (pinfunction "G_1") (pintype "passive"))
      (node (ref "R78") (pin "2") (pinfunction "2_2") (pintype "passive"))
    )
    (net (code "44") (name "EN_IF1") (class "Default")
      (node (ref "Q5") (pin "3") (pinfunction "D_3") (pintype "passive"))
      (node (ref "U$3") (pin "4") (pinfunction "4_4") (pintype "bidirectional"))
    )
    (net (code "45") (name "EN_IF2") (class "Default")
      (node (ref "Q6") (pin "3") (pinfunction "D_3") (pintype "passive"))
      (node (ref "U$8") (pin "4") (pinfunction "4_4") (pintype "bidirectional"))
    )
    (net (code "46") (name "EN_IF3") (class "Default")
      (node (ref "Q8") (pin "3") (pinfunction "D_3") (pintype "passive"))
      (node (ref "U$9") (pin "4") (pinfunction "4_4") (pintype "bidirectional"))
    )
    (net (code "47") (name "EN_IF4") (class "Default")
      (node (ref "Q9") (pin "3") (pinfunction "D_3") (pintype "passive"))
      (node (ref "U$10") (pin "4") (pinfunction "4_4") (pintype "bidirectional"))
    )
    (net (code "48") (name "EN_IF5") (class "Default")
      (node (ref "Q10") (pin "3") (pinfunction "D_3") (pintype "passive"))
      (node (ref "U$11") (pin "4") (pinfunction "4_4") (pintype "bidirectional"))
    )
    (net (code "49") (name "EN_IF6") (class "Default")
      (node (ref "Q11") (pin "3") (pinfunction "D_3") (pintype "passive"))
      (node (ref "U$12") (pin "4") (pinfunction "4_4") (pintype "bidirectional"))
    )
    (net (code "50") (name "EN_IF7") (class "Default")
      (node (ref "Q12") (pin "3") (pinfunction "D_3") (pintype "passive"))
      (node (ref "U$13") (pin "4") (pinfunction "4_4") (pintype "bidirectional"))
    )
    (net (code "51") (name "EN_IF8") (class "Default")
      (node (ref "Q13") (pin "3") (pinfunction "D_3") (pintype "passive"))
      (node (ref "U$14") (pin "4") (pinfunction "4_4") (pintype "bidirectional"))
    )
    (net (code "52") (name "EN_IF9") (class "Default")
      (node (ref "Q14") (pin "3") (pinfunction "D_3") (pintype "passive"))
      (node (ref "U$15") (pin "4") (pinfunction "4_4") (pintype "bidirectional"))
    )
    (net (code "53") (name "EN_IF10") (class "Default")
      (node (ref "Q15") (pin "3") (pinfunction "D_3") (pintype "passive"))
      (node (ref "U$16") (pin "4") (pinfunction "4_4") (pintype "bidirectional"))
    )
    (net (code "54") (name "ETH_5V") (class "Default")
      (node (ref "J2") (pin "12") (pinfunction "12_12") (pintype "passive"))
      (node (ref "R37") (pin "1") (pinfunction "1_1") (pintype "passive"))
    )
    (net (code "55") (name "ETH_CLKOUT") (class "Default")
      (node (ref "J2") (pin "9") (pinfunction "9_9") (pintype "passive"))
    )
    (net (code "56") (name "ETH_CS") (class "Default")
      (node (ref "J2") (pin "3") (pinfunction "3_3") (pintype "passive"))
      (node (ref "R48") (pin "2") (pinfunction "2_2") (pintype "passive"))
    )
    (net (code "57") (name "ETH_INT") (class "Default")
      (node (ref "J2") (pin "10") (pinfunction "10_10") (pintype "passive"))
      (node (ref "TP7") (pin "TP") (pinfunction "TP_TP") (pintype "input"))
      (node (ref "U2") (pin "4") (pinfunction "SENSOR_VP/I36_4") (pintype "bidirectional"))
    )
    (net (code "58") (name "ETH_RST") (class "Default")
      (node (ref "J2") (pin "4") (pinfunction "4_4") (pintype "passive"))
      (node (ref "U2") (pin "26") (pinfunction "IO4_26") (pintype "bidirectional"))
    )
    (net (code "59") (name "ETH_WOL") (class "Default")
      (node (ref "J2") (pin "7") (pinfunction "7_7") (pintype "passive"))
    )
    (net (code "60") (name "FAN") (class "Default")
      (node (ref "Q3") (pin "1") (pinfunction "G_1") (pintype "bidirectional"))
      (node (ref "R20") (pin "2") (pinfunction "2_2") (pintype "passive"))
      (node (ref "R21") (pin "1") (pinfunction "1_1") (pintype "passive"))
      (node (ref "TP5") (pin "TP") (pinfunction "TP_TP") (pintype "input"))
    )
    (net (code "61") (name "FAN_MCU") (class "Default")
      (node (ref "R20") (pin "1") (pinfunction "1_1") (pintype "passive"))
      (node (ref "U2") (pin "10") (pinfunction "IO25_10") (pintype "bidirectional"))
    )
    (net (code "62") (name "GND") (class "Default")
      (node (ref "C10") (pin "2") (pinfunction "2_2") (pintype "passive"))
      (node (ref "C11") (pin "2") (pinfunction "2_2") (pintype "passive"))
      (node (ref "C12") (pin "2") (pinfunction "2_2") (pintype "passive"))
      (node (ref "C14") (pin "2") (pinfunction "2_2") (pintype "passive"))
      (node (ref "C15") (pin "2") (pinfunction "2_2") (pintype "passive"))
      (node (ref "C16") (pin "2") (pinfunction "2_2") (pintype "passive"))
      (node (ref "C17") (pin "2") (pinfunction "2_2") (pintype "passive"))
      (node (ref "C2") (pin "2") (pinfunction "2_2") (pintype "passive"))
      (node (ref "C23") (pin "2") (pinfunction "2_2") (pintype "passive"))
      (node (ref "C24") (pin "2") (pinfunction "2_2") (pintype "passive"))
      (node (ref "C25") (pin "2") (pinfunction "2_2") (pintype "passive"))
      (node (ref "C26") (pin "2") (pinfunction "2_2") (pintype "passive"))
      (node (ref "C27") (pin "2") (pinfunction "2_2") (pintype "passive"))
      (node (ref "C28") (pin "2") (pinfunction "2_2") (pintype "passive"))
      (node (ref "C29") (pin "2") (pinfunction "2_2") (pintype "passive"))
      (node (ref "C3") (pin "2") (pinfunction "2_2") (pintype "passive"))
      (node (ref "C30") (pin "2") (pinfunction "2_2") (pintype "passive"))
      (node (ref "C31") (pin "2") (pinfunction "2_2") (pintype "passive"))
      (node (ref "C37") (pin "2") (pinfunction "2_2") (pintype "passive"))
      (node (ref "C38") (pin "2") (pinfunction "2_2") (pintype "passive"))
      (node (ref "C39") (pin "2") (pinfunction "2_2") (pintype "passive"))
      (node (ref "C40") (pin "2") (pinfunction "2_2") (pintype "passive"))
      (node (ref "C41") (pin "2") (pinfunction "2_2") (pintype "passive"))
      (node (ref "C42") (pin "2") (pinfunction "2_2") (pintype "passive"))
      (node (ref "C43") (pin "2") (pinfunction "2_2") (pintype "passive"))
      (node (ref "C5") (pin "2") (pinfunction "2_2") (pintype "passive"))
      (node (ref "C6") (pin "2") (pinfunction "2_2") (pintype "passive"))
      (node (ref "C7") (pin "-") (pinfunction "-_-") (pintype "passive"))
      (node (ref "C8") (pin "2") (pinfunction "2_2") (pintype "passive"))
      (node (ref "C9") (pin "2") (pinfunction "2_2") (pintype "passive"))
      (node (ref "D1") (pin "2") (pinfunction "2_2") (pintype "passive"))
      (node (ref "D2") (pin "2") (pinfunction "2_2") (pintype "passive"))
      (node (ref "D4") (pin "1") (pinfunction "1_1") (pintype "passive"))
      (node (ref "D4") (pin "2") (pinfunction "2_2") (pintype "passive"))
      (node (ref "D6") (pin "1") (pinfunction "1_1") (pintype "passive"))
      (node (ref "D6") (pin "2") (pinfunction "2_2") (pintype "passive"))
      (node (ref "FB2") (pin "1") (pinfunction "P$1_1") (pintype "passive"))
      (node (ref "FB5") (pin "2") (pinfunction "P$2_2") (pintype "passive"))
      (node (ref "FB6") (pin "2") (pinfunction "P$2_2") (pintype "passive"))
      (node (ref "FB8") (pin "1") (pinfunction "P$1_1") (pintype "passive"))
      (node (ref "IC1") (pin "3") (pinfunction "GND_3") (pintype "power_in"))
      (node (ref "IC1") (pin "EXP") (pinfunction "GND_EXP") (pintype "power_in"))
      (node (ref "IC9") (pin "1") (pinfunction "1GND_1") (pintype "bidirectional"))
      (node (ref "J2") (pin "1") (pinfunction "1_1") (pintype "passive"))
      (node (ref "J2") (pin "11") (pinfunction "11_11") (pintype "passive"))
      (node (ref "J4") (pin "3") (pinfunction "VSS1_3") (pintype "power_in"))
      (node (ref "J4") (pin "6") (pinfunction "VSS2_6") (pintype "power_in"))
      (node (ref "J4") (pin "M1") (pinfunction "GND_M1") (pintype "power_in"))
      (node (ref "J4") (pin "M2") (pinfunction "GND_M2") (pintype "power_in"))
      (node (ref "J4") (pin "M3") (pinfunction "GND_M3") (pintype "power_in"))
      (node (ref "J4") (pin "M4") (pinfunction "GND_M4") (pintype "power_in"))
      (node (ref "J5") (pin "GND") (pinfunction "GND_GND") (pintype "power_in"))
      (node (ref "J5") (pin "P1") (pinfunction "SHIELD_P1") (pintype "bidirectional"))
      (node (ref "J5") (pin "P2") (pinfunction "SHIELD_P2") (pintype "bidirectional"))
      (node (ref "J5") (pin "P3") (pinfunction "SHIELD_P3") (pintype "bidirectional"))
      (node (ref "J8") (pin "6") (pinfunction "SUPPLY_VOLTAGE_GND_6") (pintype "bidirectional"))
      (node (ref "J8") (pin "CD1") (pinfunction "CARD_DETECT_SW_1_CD1") (pintype "bidirectional"))
      (node (ref "JTAG1") (pin "3") (pinfunction "3_3") (pintype "passive"))
      (node (ref "JTAG1") (pin "5") (pinfunction "5_5") (pintype "passive"))
      (node (ref "JTAG1") (pin "7") (pinfunction "7_7") (pintype "passive"))
      (node (ref "JTAG1") (pin "9") (pinfunction "9_9") (pintype "passive"))
      (node (ref "Q3") (pin "2") (pinfunction "S_2") (pintype "bidirectional"))
      (node (ref "R21") (pin "2") (pinfunction "2_2") (pintype "passive"))
      (node (ref "R28") (pin "2") (pinfunction "2_2") (pintype "passive"))
      (node (ref "R40") (pin "1") (pinfunction "1_1") (pintype "passive"))
      (node (ref "R44") (pin "1") (pinfunction "1_1") (pintype "passive"))
      (node (ref "R50") (pin "2") (pinfunction "2_2") (pintype "passive"))
      (node (ref "R53") (pin "2") (pinfunction "2_2") (pintype "passive"))
      (node (ref "R9") (pin "2") (pinfunction "2_2") (pintype "passive"))
      (node (ref "S1") (pin "2") (pinfunction "S_2") (pintype "passive"))
      (node (ref "S_D1") (pin "2") (pinfunction "2_2") (pintype "passive"))
      (node (ref "S_D2") (pin "2") (pinfunction "2_2") (pintype "passive"))
      (node (ref "TP20") (pin "TP") (pinfunction "TP_TP") (pintype "input"))
      (node (ref "U$1") (pin "1") (pinfunction "GND_1") (pintype "bidirectional"))
      (node (ref "U$2") (pin "4") (pinfunction "4_4") (pintype "passive"))
      (node (ref "U$4") (pin "1") (pinfunction "GND_1") (pintype "bidirectional"))
      (node (ref "U1") (pin "4") (pinfunction "GND_4") (pintype "power_in"))
      (node (ref "U2") (pin "1") (pinfunction "GND_1") (pintype "bidirectional"))
      (node (ref "U2") (pin "15") (pinfunction "GND_15") (pintype "bidirectional"))
      (node (ref "U2") (pin "38") (pinfunction "GND_38") (pintype "bidirectional"))
      (node (ref "U2") (pin "GND") (pinfunction "GND_GND") (pintype "bidirectional"))
      (node (ref "U2") (pin "GND1") (pinfunction "GND_GND1") (pintype "bidirectional"))
      (node (ref "U2") (pin "GND2") (pinfunction "GND_GND2") (pintype "bidirectional"))
      (node (ref "U2") (pin "GND3") (pinfunction "GND_GND3") (pintype "bidirectional"))
      (node (ref "U2") (pin "GND4") (pinfunction "GND_GND4") (pintype "bidirectional"))
      (node (ref "U2") (pin "GND5") (pinfunction "GND_GND5") (pintype "bidirectional"))
      (node (ref "U2") (pin "GND6") (pinfunction "GND_GND6") (pintype "bidirectional"))
      (node (ref "U2") (pin "GND7") (pinfunction "GND_GND7") (pintype "bidirectional"))
      (node (ref "U2") (pin "GND8") (pinfunction "GND_GND8") (pintype "bidirectional"))
    )
    (net (code "63") (name "GNDIN") (class "Default")
      (node (ref "FB5") (pin "1") (pinfunction "P$1_1") (pintype "passive"))
      (node (ref "FB6") (pin "1") (pinfunction "P$1_1") (pintype "passive"))
      (node (ref "J3") (pin "2") (pinfunction "2_2") (pintype "passive"))
      (node (ref "J3") (pin "3") (pinfunction "3_3") (pintype "passive"))
      (node (ref "X1") (pin "2") (pinfunction "KL_2") (pintype "passive"))
    )
    (net (code "64") (name "GPIO0") (class "Default")
      (node (ref "R23") (pin "2") (pinfunction "2_2") (pintype "passive"))
      (node (ref "T1") (pin "3") (pinfunction "C_3") (pintype "passive"))
      (node (ref "U$2") (pin "6") (pinfunction "6_6") (pintype "passive"))
      (node (ref "U2") (pin "25") (pinfunction "IO0_25") (pintype "bidirectional"))
    )
    (net (code "65") (name "IN5VLDO") (class "Default")
      (node (ref "C37") (pin "1") (pinfunction "1_1") (pintype "passive"))
      (node (ref "FB10") (pin "2") (pinfunction "P$2_2") (pintype "passive"))
      (node (ref "IC9") (pin "2") (pinfunction "2_VIN_2") (pintype "bidirectional"))
    )
    (net (code "66") (name "LED") (class "Default")
      (node (ref "LED_HDR") (pin "1") (pinfunction "1_1") (pintype "passive"))
      (node (ref "U2") (pin "27") (pinfunction "IO16_27") (pintype "bidirectional"))
    )
    (net (code "67") (name "MISO") (class "Default")
      (node (ref "J2") (pin "8") (pinfunction "8_8") (pintype "passive"))
      (node (ref "J4") (pin "7") (pinfunction "DAT0/DO_7") (pintype "bidirectional"))
      (node (ref "J8") (pin "7") (pinfunction "DATE_LINE_[BIT_0]_7") (pintype "bidirectional"))
      (node (ref "R31") (pin "2") (pinfunction "2_2") (pintype "passive"))
    )
    (net (code "68") (name "MOSI") (class "Default")
      (node (ref "J2") (pin "5") (pinfunction "5_5") (pintype "passive"))
      (node (ref "J4") (pin "2") (pinfunction "CMD/DI_2") (pintype "bidirectional"))
      (node (ref "J8") (pin "3") (pinfunction "COMMAND/RESPONSE_3") (pintype "bidirectional"))
      (node (ref "R17") (pin "2") (pinfunction "2_2") (pintype "passive"))
    )
    (net (code "69") (name "MTCK") (class "Default")
      (node (ref "R13") (pin "2") (pinfunction "2_2") (pintype "passive"))
      (node (ref "U2") (pin "16") (pinfunction "MOSI_H/IO13_16") (pintype "bidirectional"))
    )
    (net (code "70") (name "MTDI") (class "Default")
      (node (ref "R10") (pin "2") (pinfunction "2_2") (pintype "passive"))
      (node (ref "R9") (pin "1") (pinfunction "1_1") (pintype "passive"))
      (node (ref "U2") (pin "14") (pinfunction "MISO_H/IO12_14") (pintype "bidirectional"))
    )
    (net (code "71") (name "MTDO") (class "Default")
      (node (ref "R12") (pin "2") (pinfunction "2_2") (pintype "passive"))
      (node (ref "U2") (pin "23") (pinfunction "CS0_H/IO15_23") (pintype "bidirectional"))
    )
    (net (code "72") (name "MTMS") (class "Default")
      (node (ref "R24") (pin "2") (pinfunction "2_2") (pintype "passive"))
      (node (ref "U2") (pin "13") (pinfunction "SCK_H/IO14_13") (pintype "bidirectional"))
    )
    (net (code "73") (name "NRST") (class "Default")
      (node (ref "C16") (pin "1") (pinfunction "1_1") (pintype "passive"))
      (node (ref "JTAG1") (pin "10") (pinfunction "10_10") (pintype "passive"))
      (node (ref "R14") (pin "1") (pinfunction "1_1") (pintype "passive"))
      (node (ref "R25") (pin "1") (pinfunction "1_1") (pintype "passive"))
      (node (ref "T2") (pin "3") (pinfunction "C_3") (pintype "passive"))
      (node (ref "TP19") (pin "TP") (pinfunction "TP_TP") (pintype "input"))
      (node (ref "U$2") (pin "1") (pinfunction "1_1") (pintype "passive"))
      (node (ref "U2") (pin "3") (pinfunction "EN_3") (pintype "bidirectional"))
    )
    (net (code "74") (name "N_RTC") (class "Default")
      (node (ref "C29") (pin "1") (pinfunction "1_1") (pintype "passive"))
      (node (ref "U2") (pin "9") (pinfunction "XTAL_N/IO33_9") (pintype "bidirectional"))
      (node (ref "Y3") (pin "P$1") (pinfunction "1_P$1") (pintype "passive"))
    )
    (net (code "75") (name "Net-(C1-Pad1)") (class "Default")
      (node (ref "C1") (pin "1") (pinfunction "1_1") (pintype "passive"))
      (node (ref "R16") (pin "1") (pinfunction "1_1") (pintype "passive"))
    )
    (net (code "76") (name "Net-(C13-Pad1)") (class "Default")
      (node (ref "C13") (pin "1") (pinfunction "1_1") (pintype "passive"))
      (node (ref "R11") (pin "1") (pinfunction "1_1") (pintype "passive"))
    )
    (net (code "77") (name "Net-(C23-Pad1)") (class "Default")
      (node (ref "C23") (pin "1") (pinfunction "1_1") (pintype "passive"))
      (node (ref "R27") (pin "2") (pinfunction "2_2") (pintype "passive"))
      (node (ref "S_D1") (pin "1") (pinfunction "1_1") (pintype "passive"))
    )
    (net (code "78") (name "Net-(C31-Pad1)") (class "Default")
      (node (ref "C31") (pin "1") (pinfunction "1_1") (pintype "passive"))
      (node (ref "R26") (pin "2") (pinfunction "2_2") (pintype "passive"))
      (node (ref "S_D2") (pin "1") (pinfunction "1_1") (pintype "passive"))
    )
    (net (code "79") (name "Net-(IC1-RXD)") (class "Default")
      (node (ref "IC1") (pin "25") (pinfunction "RXD_25") (pintype "input"))
      (node (ref "R4") (pin "2") (pinfunction "2_2") (pintype "passive"))
    )
    (net (code "80") (name "Net-(IC1-TXD)") (class "Default")
      (node (ref "IC1") (pin "26") (pinfunction "TXD_26") (pintype "output"))
      (node (ref "R3") (pin "2") (pinfunction "2_2") (pintype "passive"))
    )
    (net (code "81") (name "Net-(IC1-VBUS)") (class "Default")
      (node (ref "IC1") (pin "8") (pinfunction "VBUS_8") (pintype "input"))
      (node (ref "R43") (pin "1") (pinfunction "1_1") (pintype "passive"))
      (node (ref "R44") (pin "2") (pinfunction "2_2") (pintype "passive"))
    )
    (net (code "82") (name "Net-(IC1-~{RST})") (class "Default")
      (node (ref "IC1") (pin "9") (pinfunction "~{RST}_9") (pintype "bidirectional"))
      (node (ref "R42") (pin "2") (pinfunction "2_2") (pintype "passive"))
    )
    (net (code "83") (name "Net-(IC2-AIN0)") (class "Default")
      (node (ref "IC2") (pin "4") (pinfunction "AIN0_4") (pintype "bidirectional"))
      (node (ref "J9") (pin "3") (pinfunction "3_3") (pintype "passive"))
    )
    (net (code "84") (name "Net-(IC2-AIN3)") (class "Default")
      (node (ref "IC2") (pin "7") (pinfunction "AIN3_7") (pintype "bidirectional"))
      (node (ref "J9") (pin "2") (pinfunction "2_2") (pintype "passive"))
    )
    (net (code "85") (name "Net-(IC2-ALERT{slash}RDY)") (class "Default")
      (node (ref "IC2") (pin "2") (pinfunction "ALERT/RDY_2") (pintype "bidirectional"))
      (node (ref "TP21") (pin "TP") (pinfunction "TP_TP") (pintype "input"))
    )
    (net (code "86") (name "Net-(IC4-ALERT{slash}RDY)") (class "Default")
      (node (ref "IC4") (pin "2") (pinfunction "ALERT/RDY_2") (pintype "bidirectional"))
      (node (ref "TP12") (pin "TP") (pinfunction "TP_TP") (pintype "input"))
    )
    (net (code "87") (name "Net-(IC5-ALERT{slash}RDY)") (class "Default")
      (node (ref "IC5") (pin "2") (pinfunction "ALERT/RDY_2") (pintype "bidirectional"))
      (node (ref "TP10") (pin "TP") (pinfunction "TP_TP") (pintype "input"))
    )
    (net (code "88") (name "Net-(IC8-A2)") (class "Default")
      (node (ref "IC8") (pin "3") (pinfunction "A2_3") (pintype "input"))
      (node (ref "R35") (pin "1") (pinfunction "1_1") (pintype "passive"))
      (node (ref "R36") (pin "2") (pinfunction "2_2") (pintype "passive"))
    )
    (net (code "89") (name "Net-(IC8-I{slash}O1.0)") (class "Default")
      (node (ref "IC8") (pin "13") (pinfunction "I/O1.0_13") (pintype "bidirectional"))
      (node (ref "TP14") (pin "TP") (pinfunction "TP_TP") (pintype "input"))
    )
    (net (code "90") (name "Net-(IC8-I{slash}O1.1)") (class "Default")
      (node (ref "IC8") (pin "14") (pinfunction "I/O1.1_14") (pintype "bidirectional"))
      (node (ref "TP15") (pin "TP") (pinfunction "TP_TP") (pintype "input"))
    )
    (net (code "91") (name "Net-(IC8-I{slash}O1.2)") (class "Default")
      (node (ref "IC8") (pin "15") (pinfunction "I/O1.2_15") (pintype "bidirectional"))
      (node (ref "TP16") (pin "TP") (pinfunction "TP_TP") (pintype "input"))
    )
    (net (code "92") (name "Net-(IC8-I{slash}O1.3)") (class "Default")
      (node (ref "IC8") (pin "16") (pinfunction "I/O1.3_16") (pintype "bidirectional"))
      (node (ref "TP17") (pin "TP") (pinfunction "TP_TP") (pintype "input"))
    )
    (net (code "93") (name "Net-(IC8-~{INT})") (class "Default")
      (node (ref "IC8") (pin "1") (pinfunction "~{INT}_1") (pintype "output"))
      (node (ref "TP13") (pin "TP") (pinfunction "TP_TP") (pintype "input"))
    )
    (net (code "94") (name "Net-(JTAG1-Pad1)") (class "Default")
      (node (ref "JTAG1") (pin "1") (pinfunction "1_1") (pintype "passive"))
      (node (ref "R8") (pin "1") (pinfunction "1_1") (pintype "passive"))
    )
    (net (code "95") (name "Net-(JTAG1-Pad2)") (class "Default")
      (node (ref "JTAG1") (pin "2") (pinfunction "2_2") (pintype "passive"))
      (node (ref "R24") (pin "1") (pinfunction "1_1") (pintype "passive"))
    )
    (net (code "96") (name "Net-(JTAG1-Pad4)") (class "Default")
      (node (ref "JTAG1") (pin "4") (pinfunction "4_4") (pintype "passive"))
      (node (ref "R13") (pin "1") (pinfunction "1_1") (pintype "passive"))
    )
    (net (code "97") (name "Net-(JTAG1-Pad6)") (class "Default")
      (node (ref "JTAG1") (pin "6") (pinfunction "6_6") (pintype "passive"))
      (node (ref "R12") (pin "1") (pinfunction "1_1") (pintype "passive"))
    )
    (net (code "98") (name "Net-(JTAG1-Pad8)") (class "Default")
      (node (ref "JTAG1") (pin "8") (pinfunction "8_8") (pintype "passive"))
      (node (ref "R10") (pin "1") (pinfunction "1_1") (pintype "passive"))
    )
    (net (code "99") (name "Net-(L2-1)") (class "Default")
      (node (ref "C1") (pin "2") (pinfunction "2_2") (pintype "passive"))
      (node (ref "L2") (pin "P$1") (pinfunction "1_P$1") (pintype "passive"))
      (node (ref "U$4") (pin "2") (pinfunction "SW_2") (pintype "bidirectional"))
    )
    (net (code "100") (name "Net-(L3-1)") (class "Default")
      (node (ref "C13") (pin "2") (pinfunction "2_2") (pintype "passive"))
      (node (ref "L3") (pin "P$1") (pinfunction "1_P$1") (pintype "passive"))
      (node (ref "U$1") (pin "2") (pinfunction "SW_2") (pintype "bidirectional"))
    )
    (net (code "101") (name "Net-(LED_HDR-Pad2)") (class "Default")
      (node (ref "LED_HDR") (pin "2") (pinfunction "2_2") (pintype "passive"))
      (node (ref "R19") (pin "1") (pinfunction "1_1") (pintype "passive"))
    )
    (net (code "102") (name "Net-(Q3-D)") (class "Default")
      (node (ref "FAN_5V") (pin "1") (pinfunction "1_1") (pintype "passive"))
      (node (ref "Q3") (pin "3") (pinfunction "D_3") (pintype "bidirectional"))
    )
    (net (code "103") (name "Net-(R7-Pad2)") (class "Default")
      (node (ref "R7") (pin "2") (pinfunction "2_2") (pintype "passive"))
      (node (ref "U$2") (pin "2") (pinfunction "2_2") (pintype "passive"))
    )
    (net (code "104") (name "Net-(T1-B)") (class "Default")
      (node (ref "R2") (pin "1") (pinfunction "1_1") (pintype "passive"))
      (node (ref "T1") (pin "1") (pinfunction "B_1") (pintype "passive"))
    )
    (net (code "105") (name "Net-(T2-B)") (class "Default")
      (node (ref "R1") (pin "1") (pinfunction "1_1") (pintype "passive"))
      (node (ref "T2") (pin "1") (pinfunction "B_1") (pintype "passive"))
    )
    (net (code "106") (name "Net-(U$1-EN)") (class "Default")
      (node (ref "R49") (pin "1") (pinfunction "1_1") (pintype "passive"))
      (node (ref "TP4") (pin "TP") (pinfunction "TP_TP") (pintype "input"))
      (node (ref "U$1") (pin "5") (pinfunction "EN_5") (pintype "bidirectional"))
    )
    (net (code "107") (name "Net-(U$1-VBST)") (class "Default")
      (node (ref "R11") (pin "2") (pinfunction "2_2") (pintype "passive"))
      (node (ref "U$1") (pin "6") (pinfunction "VBST_6") (pintype "bidirectional"))
    )
    (net (code "108") (name "Net-(U$1-VFB)") (class "Default")
      (node (ref "R50") (pin "1") (pinfunction "1_1") (pintype "passive"))
      (node (ref "R51") (pin "1") (pinfunction "1_1") (pintype "passive"))
      (node (ref "R52") (pin "1") (pinfunction "1_1") (pintype "passive"))
      (node (ref "U$1") (pin "4") (pinfunction "VFB_4") (pintype "bidirectional"))
    )
    (net (code "109") (name "Net-(U$4-EN)") (class "Default")
      (node (ref "R22") (pin "1") (pinfunction "1_1") (pintype "passive"))
      (node (ref "TP1") (pin "TP") (pinfunction "TP_TP") (pintype "input"))
      (node (ref "U$4") (pin "5") (pinfunction "EN_5") (pintype "bidirectional"))
    )
    (net (code "110") (name "Net-(U$4-VBST)") (class "Default")
      (node (ref "R16") (pin "2") (pinfunction "2_2") (pintype "passive"))
      (node (ref "U$4") (pin "6") (pinfunction "VBST_6") (pintype "bidirectional"))
    )
    (net (code "111") (name "Net-(U$4-VFB)") (class "Default")
      (node (ref "R28") (pin "1") (pinfunction "1_1") (pintype "passive"))
      (node (ref "R29") (pin "1") (pinfunction "1_1") (pintype "passive"))
      (node (ref "R30") (pin "1") (pinfunction "1_1") (pintype "passive"))
      (node (ref "U$4") (pin "4") (pinfunction "VFB_4") (pintype "bidirectional"))
    )
    (net (code "112") (name "Net-(U2-IO26)") (class "Default")
      (node (ref "TP8") (pin "TP") (pinfunction "TP_TP") (pintype "input"))
      (node (ref "U2") (pin "11") (pinfunction "IO26_11") (pintype "bidirectional"))
    )
    (net (code "113") (name "Net-(U2-IO27)") (class "Default")
      (node (ref "TP9") (pin "TP") (pinfunction "TP_TP") (pintype "input"))
      (node (ref "U2") (pin "12") (pinfunction "IO27_12") (pintype "bidirectional"))
    )
    (net (code "114") (name "Net-(U2-SENSOR_VN{slash}I39)") (class "Default")
      (node (ref "TP6") (pin "TP") (pinfunction "TP_TP") (pintype "input"))
      (node (ref "U2") (pin "5") (pinfunction "SENSOR_VN/I39_5") (pintype "bidirectional"))
    )
    (net (code "115") (name "P_RTC") (class "Default")
      (node (ref "C30") (pin "1") (pinfunction "1_1") (pintype "passive"))
      (node (ref "U2") (pin "8") (pinfunction "XTAL_P/IO32_8") (pintype "bidirectional"))
      (node (ref "Y3") (pin "P$2") (pinfunction "2_P$2") (pintype "passive"))
    )
    (net (code "116") (name "RTS") (class "Default")
      (node (ref "IC1") (pin "24") (pinfunction "RTS_24") (pintype "output"))
      (node (ref "R2") (pin "2") (pinfunction "2_2") (pintype "passive"))
      (node (ref "T2") (pin "2") (pinfunction "E_2") (pintype "passive"))
    )
    (net (code "117") (name "RXD0") (class "Default")
      (node (ref "R3") (pin "1") (pinfunction "1_1") (pintype "passive"))
      (node (ref "U$2") (pin "5") (pinfunction "5_5") (pintype "passive"))
      (node (ref "U2") (pin "34") (pinfunction "RXD_34") (pintype "bidirectional"))
    )
    (net (code "118") (name "SCL") (class "Default")
      (node (ref "R47") (pin "2") (pinfunction "2_2") (pintype "passive"))
      (node (ref "S_D1") (pin "3") (pinfunction "3_3") (pintype "passive"))
      (node (ref "S_D2") (pin "3") (pinfunction "3_3") (pintype "passive"))
      (node (ref "U1") (pin "3") (pinfunction "A2_3") (pintype "bidirectional"))
    )
    (net (code "119") (name "SCLK") (class "Default")
      (node (ref "J2") (pin "6") (pinfunction "6_6") (pintype "passive"))
      (node (ref "J4") (pin "5") (pinfunction "CLK/SCLK_5") (pintype "bidirectional"))
      (node (ref "J8") (pin "5") (pinfunction "CLOCK_5") (pintype "bidirectional"))
      (node (ref "R55") (pin "2") (pinfunction "2_2") (pintype "passive"))
    )
    (net (code "120") (name "SCL_5V") (class "Default")
      (node (ref "IC2") (pin "1") (pinfunction "ADDR_1") (pintype "bidirectional"))
      (node (ref "IC2") (pin "10") (pinfunction "SCL_10") (pintype "bidirectional"))
      (node (ref "IC3") (pin "6") (pinfunction "SY_6") (pintype "bidirectional"))
      (node (ref "IC4") (pin "10") (pinfunction "SCL_10") (pintype "bidirectional"))
      (node (ref "IC5") (pin "10") (pinfunction "SCL_10") (pintype "bidirectional"))
      (node (ref "IC8") (pin "22") (pinfunction "SCL_22") (pintype "input"))
      (node (ref "R82") (pin "2") (pinfunction "2_2") (pintype "passive"))
      (node (ref "U1") (pin "6") (pinfunction "B2_6") (pintype "bidirectional"))
    )
    (net (code "121") (name "SCL_BUFF") (class "Default")
      (node (ref "IC3") (pin "7") (pinfunction "LY_7") (pintype "bidirectional"))
      (node (ref "R34") (pin "2") (pinfunction "2_2") (pintype "passive"))
      (node (ref "U$10") (pin "6") (pinfunction "6_6") (pintype "bidirectional"))
      (node (ref "U$11") (pin "6") (pinfunction "6_6") (pintype "bidirectional"))
      (node (ref "U$12") (pin "6") (pinfunction "6_6") (pintype "bidirectional"))
      (node (ref "U$13") (pin "6") (pinfunction "6_6") (pintype "bidirectional"))
      (node (ref "U$14") (pin "6") (pinfunction "6_6") (pintype "bidirectional"))
      (node (ref "U$15") (pin "6") (pinfunction "6_6") (pintype "bidirectional"))
      (node (ref "U$16") (pin "6") (pinfunction "6_6") (pintype "bidirectional"))
      (node (ref "U$3") (pin "6") (pinfunction "6_6") (pintype "bidirectional"))
      (node (ref "U$8") (pin "6") (pinfunction "6_6") (pintype "bidirectional"))
      (node (ref "U$9") (pin "6") (pinfunction "6_6") (pintype "bidirectional"))
    )
    (net (code "122") (name "SCL_MCU") (class "Default")
      (node (ref "R47") (pin "1") (pinfunction "1_1") (pintype "passive"))
      (node (ref "U2") (pin "36") (pinfunction "IO22_36") (pintype "bidirectional"))
    )
    (net (code "123") (name "SDA") (class "Default")
      (node (ref "R32") (pin "2") (pinfunction "2_2") (pintype "passive"))
      (node (ref "S_D1") (pin "4") (pinfunction "4_4") (pintype "passive"))
      (node (ref "S_D2") (pin "4") (pinfunction "4_4") (pintype "passive"))
      (node (ref "U1") (pin "2") (pinfunction "A1_2") (pintype "bidirectional"))
    )
    (net (code "124") (name "SDA_5V") (class "Default")
      (node (ref "IC2") (pin "9") (pinfunction "SDA_9") (pintype "bidirectional"))
      (node (ref "IC3") (pin "3") (pinfunction "SX_3") (pintype "bidirectional"))
      (node (ref "IC4") (pin "9") (pinfunction "SDA_9") (pintype "bidirectional"))
      (node (ref "IC5") (pin "1") (pinfunction "ADDR_1") (pintype "bidirectional"))
      (node (ref "IC5") (pin "9") (pinfunction "SDA_9") (pintype "bidirectional"))
      (node (ref "IC8") (pin "23") (pinfunction "SDA_23") (pintype "bidirectional"))
      (node (ref "R81") (pin "2") (pinfunction "2_2") (pintype "passive"))
      (node (ref "U1") (pin "7") (pinfunction "B1_7") (pintype "bidirectional"))
    )
    (net (code "125") (name "SDA_BUFF") (class "Default")
      (node (ref "IC3") (pin "2") (pinfunction "LX_2") (pintype "bidirectional"))
      (node (ref "R33") (pin "2") (pinfunction "2_2") (pintype "passive"))
      (node (ref "U$10") (pin "5") (pinfunction "5_5") (pintype "bidirectional"))
      (node (ref "U$11") (pin "5") (pinfunction "5_5") (pintype "bidirectional"))
      (node (ref "U$12") (pin "5") (pinfunction "5_5") (pintype "bidirectional"))
      (node (ref "U$13") (pin "5") (pinfunction "5_5") (pintype "bidirectional"))
      (node (ref "U$14") (pin "5") (pinfunction "5_5") (pintype "bidirectional"))
      (node (ref "U$15") (pin "5") (pinfunction "5_5") (pintype "bidirectional"))
      (node (ref "U$16") (pin "5") (pinfunction "5_5") (pintype "bidirectional"))
      (node (ref "U$3") (pin "5") (pinfunction "5_5") (pintype "bidirectional"))
      (node (ref "U$8") (pin "5") (pinfunction "5_5") (pintype "bidirectional"))
      (node (ref "U$9") (pin "5") (pinfunction "5_5") (pintype "bidirectional"))
    )
    (net (code "126") (name "SDA_MCU") (class "Default")
      (node (ref "R32") (pin "1") (pinfunction "1_1") (pintype "passive"))
      (node (ref "U2") (pin "33") (pinfunction "IO21_33") (pintype "bidirectional"))
    )
    (net (code "127") (name "SD_CD") (class "Default")
      (node (ref "J4") (pin "10") (pinfunction "CDI#_10") (pintype "output"))
      (node (ref "J8") (pin "CD2") (pinfunction "CARD_DETECT_SW_2_CD2") (pintype "bidirectional"))
      (node (ref "R64") (pin "1") (pinfunction "1_1") (pintype "passive"))
    )
    (net (code "128") (name "SD_CS") (class "Default")
      (node (ref "J4") (pin "1") (pinfunction "CD/DAT3/CS_1") (pintype "bidirectional"))
      (node (ref "J8") (pin "2") (pinfunction "CARD_DETECT_/_DATE_LINE_[BIT_3]_2") (pintype "bidirectional"))
      (node (ref "R63") (pin "2") (pinfunction "2_2") (pintype "passive"))
    )
    (net (code "129") (name "SD_CS_MCU") (class "Default")
      (node (ref "R63") (pin "1") (pinfunction "1_1") (pintype "passive"))
      (node (ref "U2") (pin "28") (pinfunction "IO17_28") (pintype "bidirectional"))
    )
    (net (code "130") (name "SD_VDD") (class "Default")
      (node (ref "C38") (pin "1") (pinfunction "1_1") (pintype "passive"))
      (node (ref "J4") (pin "4") (pinfunction "VDD_4") (pintype "power_in"))
      (node (ref "J8") (pin "4") (pinfunction "SUPPLY_VOLTAGE_4") (pintype "bidirectional"))
      (node (ref "R65") (pin "1") (pinfunction "1_1") (pintype "passive"))
    )
    (net (code "131") (name "TXD0") (class "Default")
      (node (ref "R4") (pin "1") (pinfunction "1_1") (pintype "passive"))
      (node (ref "U$2") (pin "3") (pinfunction "3_3") (pintype "passive"))
      (node (ref "U2") (pin "35") (pinfunction "TXD_35") (pintype "bidirectional"))
    )
    (net (code "132") (name "VGI") (class "Default")
      (node (ref "Q2") (pin "1") (pinfunction "G_1") (pintype "passive"))
      (node (ref "Q7") (pin "1") (pinfunction "G_1") (pintype "passive"))
      (node (ref "R53") (pin "1") (pinfunction "1_1") (pintype "passive"))
      (node (ref "R54") (pin "2") (pinfunction "2_2") (pintype "passive"))
    )
    (net (code "133") (name "VIN") (class "Default")
      (node (ref "C28") (pin "1") (pinfunction "1_1") (pintype "passive"))
      (node (ref "D4") (pin "3") (pinfunction "3_3") (pintype "passive"))
      (node (ref "FB3") (pin "2") (pinfunction "P$2_2") (pintype "passive"))
      (node (ref "FB4") (pin "2") (pinfunction "P$2_2") (pintype "passive"))
      (node (ref "Q2") (pin "3") (pinfunction "D_3") (pintype "passive"))
      (node (ref "Q7") (pin "3") (pinfunction "D_3") (pintype "passive"))
      (node (ref "R54") (pin "1") (pinfunction "1_1") (pintype "passive"))
    )
    (net (code "134") (name "VIN_IN") (class "Default")
      (node (ref "FB3") (pin "1") (pinfunction "P$1_1") (pintype "passive"))
      (node (ref "FB4") (pin "1") (pinfunction "P$1_1") (pintype "passive"))
      (node (ref "J3") (pin "1") (pinfunction "1_1") (pintype "passive"))
      (node (ref "X1") (pin "1") (pinfunction "KL_1") (pintype "passive"))
    )
    (net (code "135") (name "VIN_PROTECTED") (class "Default")
      (node (ref "C14") (pin "1") (pinfunction "1_1") (pintype "passive"))
      (node (ref "C15") (pin "1") (pinfunction "1_1") (pintype "passive"))
      (node (ref "C6") (pin "1") (pinfunction "1_1") (pintype "passive"))
      (node (ref "C7") (pin "+") (pinfunction "+_+") (pintype "passive"))
      (node (ref "C9") (pin "1") (pinfunction "1_1") (pintype "passive"))
      (node (ref "FB10") (pin "1") (pinfunction "P$1_1") (pintype "passive"))
      (node (ref "Q2") (pin "2") (pinfunction "S_2") (pintype "passive"))
      (node (ref "Q7") (pin "2") (pinfunction "S_2") (pintype "passive"))
      (node (ref "R22") (pin "2") (pinfunction "2_2") (pintype "passive"))
      (node (ref "R49") (pin "2") (pinfunction "2_2") (pintype "passive"))
      (node (ref "TP11") (pin "TP") (pinfunction "TP_TP") (pintype "input"))
      (node (ref "U$1") (pin "3") (pinfunction "VIN_3") (pintype "bidirectional"))
      (node (ref "U$4") (pin "3") (pinfunction "VIN_3") (pintype "bidirectional"))
    )
    (net (code "136") (name "VSPI_CS_ETH") (class "Default")
      (node (ref "R48") (pin "1") (pinfunction "1_1") (pintype "passive"))
      (node (ref "U2") (pin "37") (pinfunction "MOSI_V/IO23_37") (pintype "bidirectional"))
    )
    (net (code "137") (name "VSPI_MISO") (class "Default")
      (node (ref "R31") (pin "1") (pinfunction "1_1") (pintype "passive"))
      (node (ref "U2") (pin "31") (pinfunction "MISO_V/IO19_31") (pintype "bidirectional"))
    )
    (net (code "138") (name "VSPI_MOSI") (class "Default")
      (node (ref "R17") (pin "1") (pinfunction "1_1") (pintype "passive"))
      (node (ref "U2") (pin "30") (pinfunction "SCK_V/IO18_30") (pintype "bidirectional"))
    )
    (net (code "139") (name "VSPI_SCK") (class "Default")
      (node (ref "R55") (pin "1") (pinfunction "1_1") (pintype "passive"))
      (node (ref "U2") (pin "29") (pinfunction "CS0_V/IO5_29") (pintype "bidirectional"))
    )
    (net (code "140") (name "V_USB") (class "Default")
      (node (ref "C5") (pin "1") (pinfunction "1_1") (pintype "passive"))
      (node (ref "D1") (pin "1") (pinfunction "1_1") (pintype "passive"))
      (node (ref "D2") (pin "1") (pinfunction "1_1") (pintype "passive"))
      (node (ref "J5") (pin "VBUS") (pinfunction "VBUS_VBUS") (pintype "power_in"))
      (node (ref "R43") (pin "2") (pinfunction "2_2") (pintype "passive"))
    )
    (net (code "141") (name "unconnected-(IC1-CTS-Pad23)") (class "Default")
      (node (ref "IC1") (pin "23") (pinfunction "CTS_23") (pintype "input"))
    )
    (net (code "142") (name "unconnected-(IC1-DCD-Pad1)") (class "Default")
      (node (ref "IC1") (pin "1") (pinfunction "DCD_1") (pintype "input"))
    )
    (net (code "143") (name "unconnected-(IC1-DSR-Pad27)") (class "Default")
      (node (ref "IC1") (pin "27") (pinfunction "DSR_27") (pintype "input"))
    )
    (net (code "144") (name "unconnected-(IC1-RI-Pad2)") (class "Default")
      (node (ref "IC1") (pin "2") (pinfunction "RI_2") (pintype "input"))
    )
    (net (code "145") (name "unconnected-(IC1-SUSPEND-Pad12)") (class "Default")
      (node (ref "IC1") (pin "12") (pinfunction "SUSPEND_12") (pintype "output"))
    )
    (net (code "146") (name "unconnected-(IC3-NC_1-Pad1)") (class "Default")
      (node (ref "IC3") (pin "1") (pinfunction "NC_1_1") (pintype "bidirectional"))
    )
    (net (code "147") (name "unconnected-(IC3-NC_2-Pad5)") (class "Default")
      (node (ref "IC3") (pin "5") (pinfunction "NC_2_5") (pintype "bidirectional"))
    )
    (net (code "148") (name "unconnected-(IC8-I{slash}O1.4-Pad17)") (class "Default")
      (node (ref "IC8") (pin "17") (pinfunction "I/O1.4_17") (pintype "bidirectional"))
    )
    (net (code "149") (name "unconnected-(IC8-I{slash}O1.5-Pad18)") (class "Default")
      (node (ref "IC8") (pin "18") (pinfunction "I/O1.5_18") (pintype "bidirectional"))
    )
    (net (code "150") (name "unconnected-(J4-DAT1-Pad8)") (class "Default")
      (node (ref "J4") (pin "8") (pinfunction "DAT1_8") (pintype "bidirectional"))
    )
    (net (code "151") (name "unconnected-(J4-DAT2-Pad9)") (class "Default")
      (node (ref "J4") (pin "9") (pinfunction "DAT2_9") (pintype "bidirectional"))
    )
    (net (code "152") (name "unconnected-(J4-WP-Pad11)") (class "Default")
      (node (ref "J4") (pin "11") (pinfunction "WP_11") (pintype "output"))
    )
    (net (code "153") (name "unconnected-(J5-PadID)") (class "Default")
      (node (ref "J5") (pin "ID") (pinfunction "ID_ID") (pintype "bidirectional"))
    )
    (net (code "154") (name "unconnected-(J8-DATE_LINE_[BIT_1]-Pad8)") (class "Default")
      (node (ref "J8") (pin "8") (pinfunction "DATE_LINE_[BIT_1]_8") (pintype "bidirectional"))
    )
    (net (code "155") (name "unconnected-(J8-DATE_LINE_[BIT_2]-Pad1)") (class "Default")
      (node (ref "J8") (pin "1") (pinfunction "DATE_LINE_[BIT_2]_1") (pintype "bidirectional"))
    )
    (net (code "156") (name "unconnected-(J8-Pad9)") (class "Default")
      (node (ref "J8") (pin "9") (pinfunction "9_9") (pintype "bidirectional"))
    )
    (net (code "157") (name "unconnected-(J8-Pad10)") (class "Default")
      (node (ref "J8") (pin "10") (pinfunction "10_10") (pintype "bidirectional"))
    )
    (net (code "158") (name "unconnected-(J8-Pad11)") (class "Default")
      (node (ref "J8") (pin "11") (pinfunction "11_11") (pintype "bidirectional"))
    )
    (net (code "159") (name "unconnected-(J8-Pad12)") (class "Default")
      (node (ref "J8") (pin "12") (pinfunction "12_12") (pintype "bidirectional"))
    )
    (net (code "160") (name "unconnected-(U2-IO2-Pad24)") (class "Default")
      (node (ref "U2") (pin "24") (pinfunction "IO2_24") (pintype "bidirectional"))
    )
    (net (code "161") (name "unconnected-(U2-IO35-Pad7)") (class "Default")
      (node (ref "U2") (pin "7") (pinfunction "IO35_7") (pintype "bidirectional"))
    )
    (net (code "162") (name "unconnected-(U2-NC-Pad32)") (class "Default")
      (node (ref "U2") (pin "32") (pinfunction "NC_32") (pintype "bidirectional"))
    )
    (net (code "163") (name "unconnected-(U2-SCK{slash}IO6-Pad20)") (class "Default")
      (node (ref "U2") (pin "20") (pinfunction "SCK/IO6_20") (pintype "bidirectional"))
    )
    (net (code "164") (name "unconnected-(U2-SCS{slash}IO11-Pad19)") (class "Default")
      (node (ref "U2") (pin "19") (pinfunction "SCS/IO11_19") (pintype "bidirectional"))
    )
    (net (code "165") (name "unconnected-(U2-SDI{slash}IO8-Pad22)") (class "Default")
      (node (ref "U2") (pin "22") (pinfunction "SDI/IO8_22") (pintype "bidirectional"))
    )
    (net (code "166") (name "unconnected-(U2-SDO{slash}IO7-Pad21)") (class "Default")
      (node (ref "U2") (pin "21") (pinfunction "SDO/IO7_21") (pintype "bidirectional"))
    )
    (net (code "167") (name "unconnected-(U2-SHD{slash}IO9-Pad17)") (class "Default")
      (node (ref "U2") (pin "17") (pinfunction "SHD/IO9_17") (pintype "bidirectional"))
    )
    (net (code "168") (name "unconnected-(U2-SWP{slash}IO10-Pad18)") (class "Default")
      (node (ref "U2") (pin "18") (pinfunction "SWP/IO10_18") (pintype "bidirectional"))
    )
  )
)
